# stereo_mix_back_digital.net
KiCad netlist of a schematic drawn in EAGLE
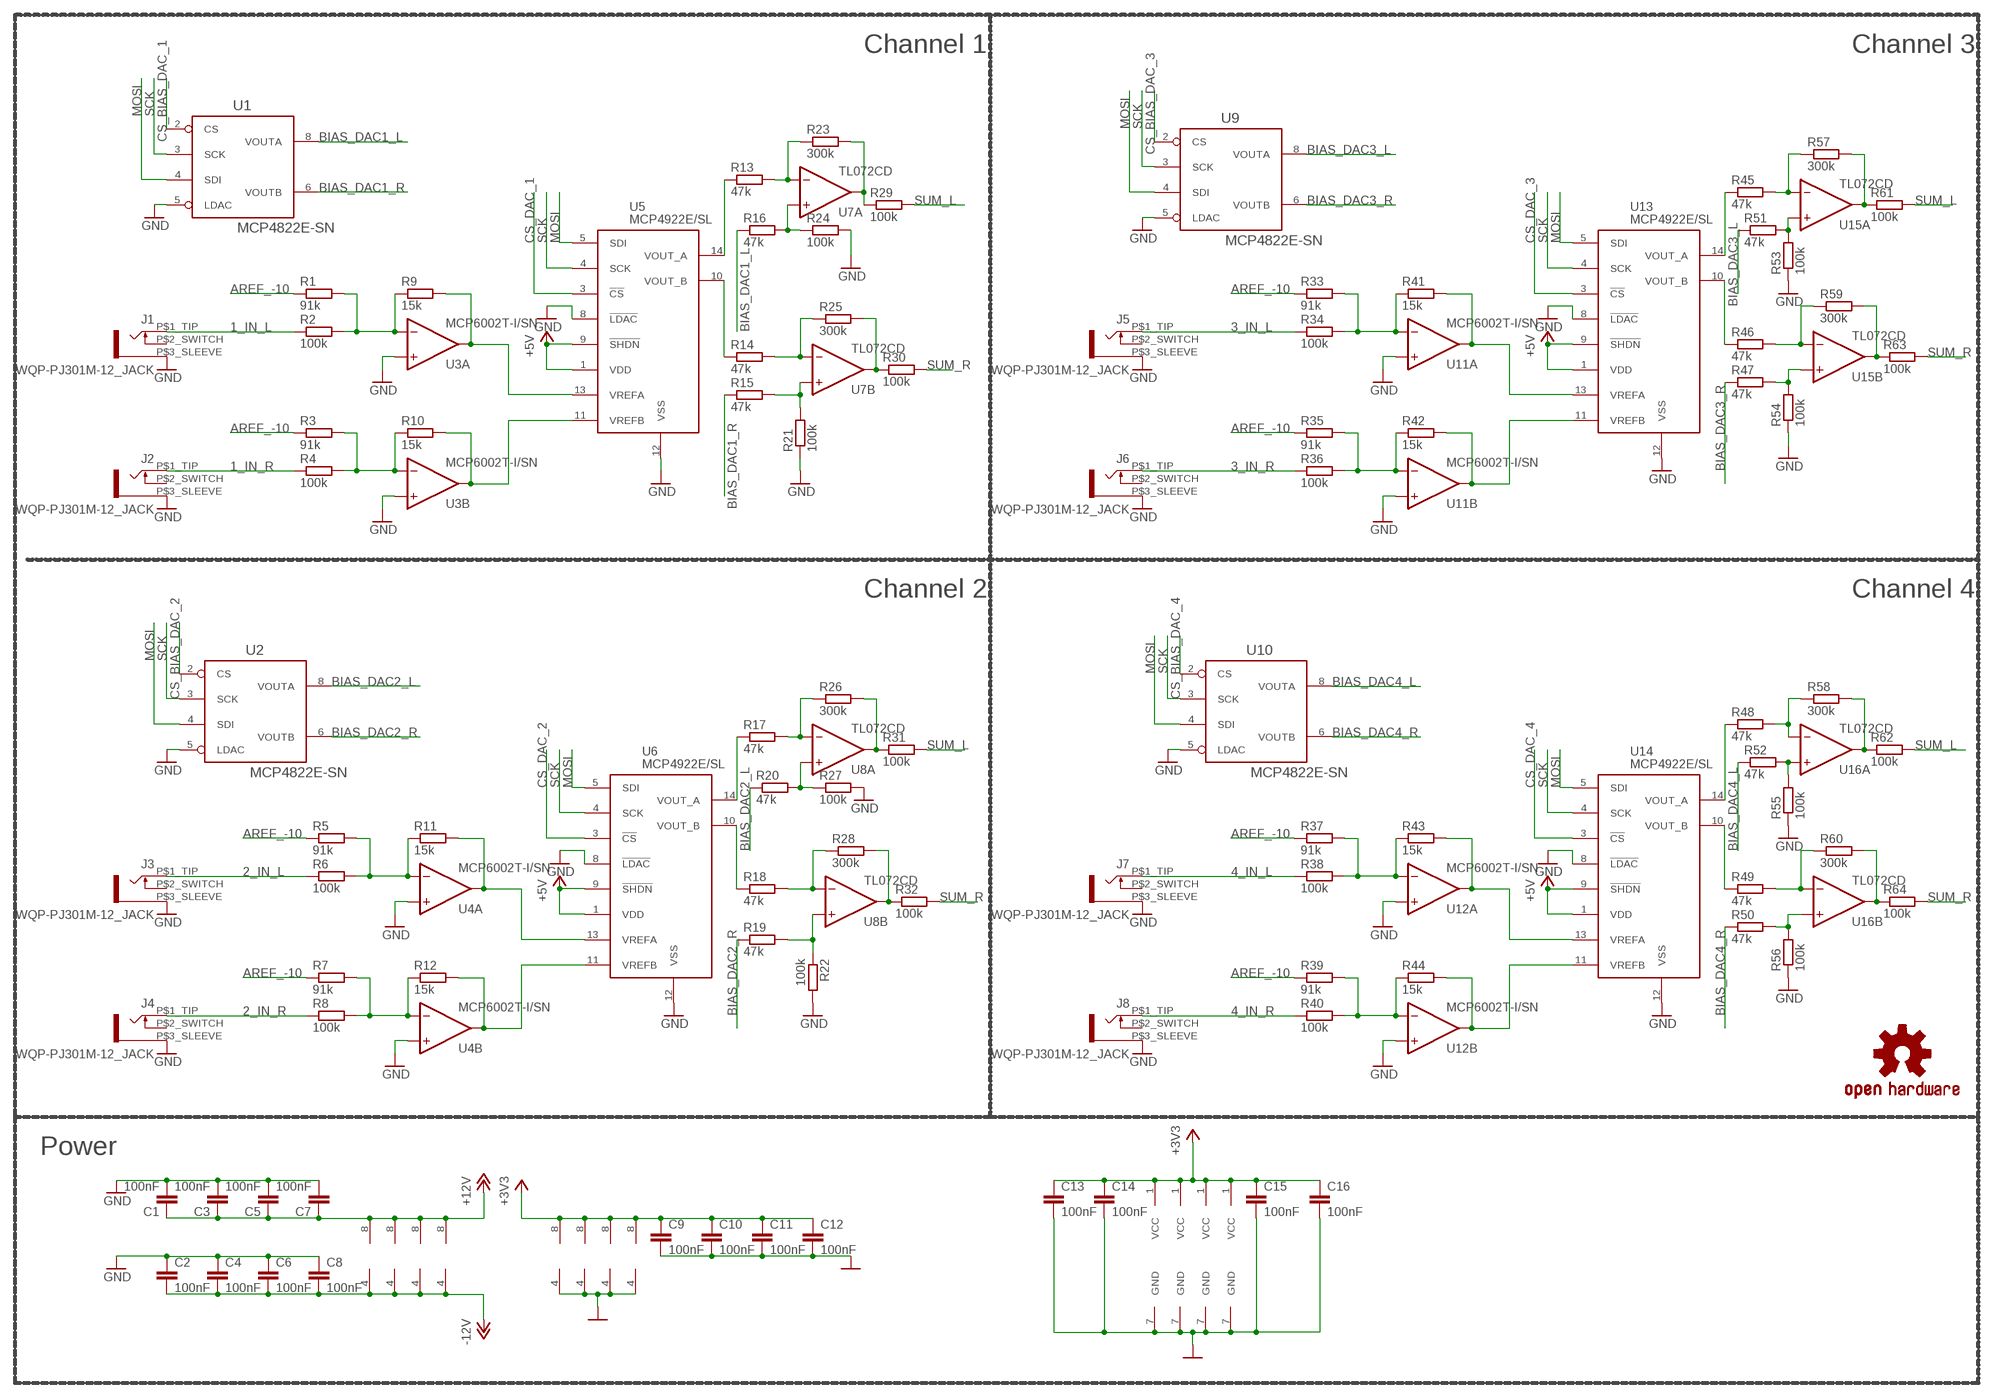
[diagram p0: schematic, sheet 1]
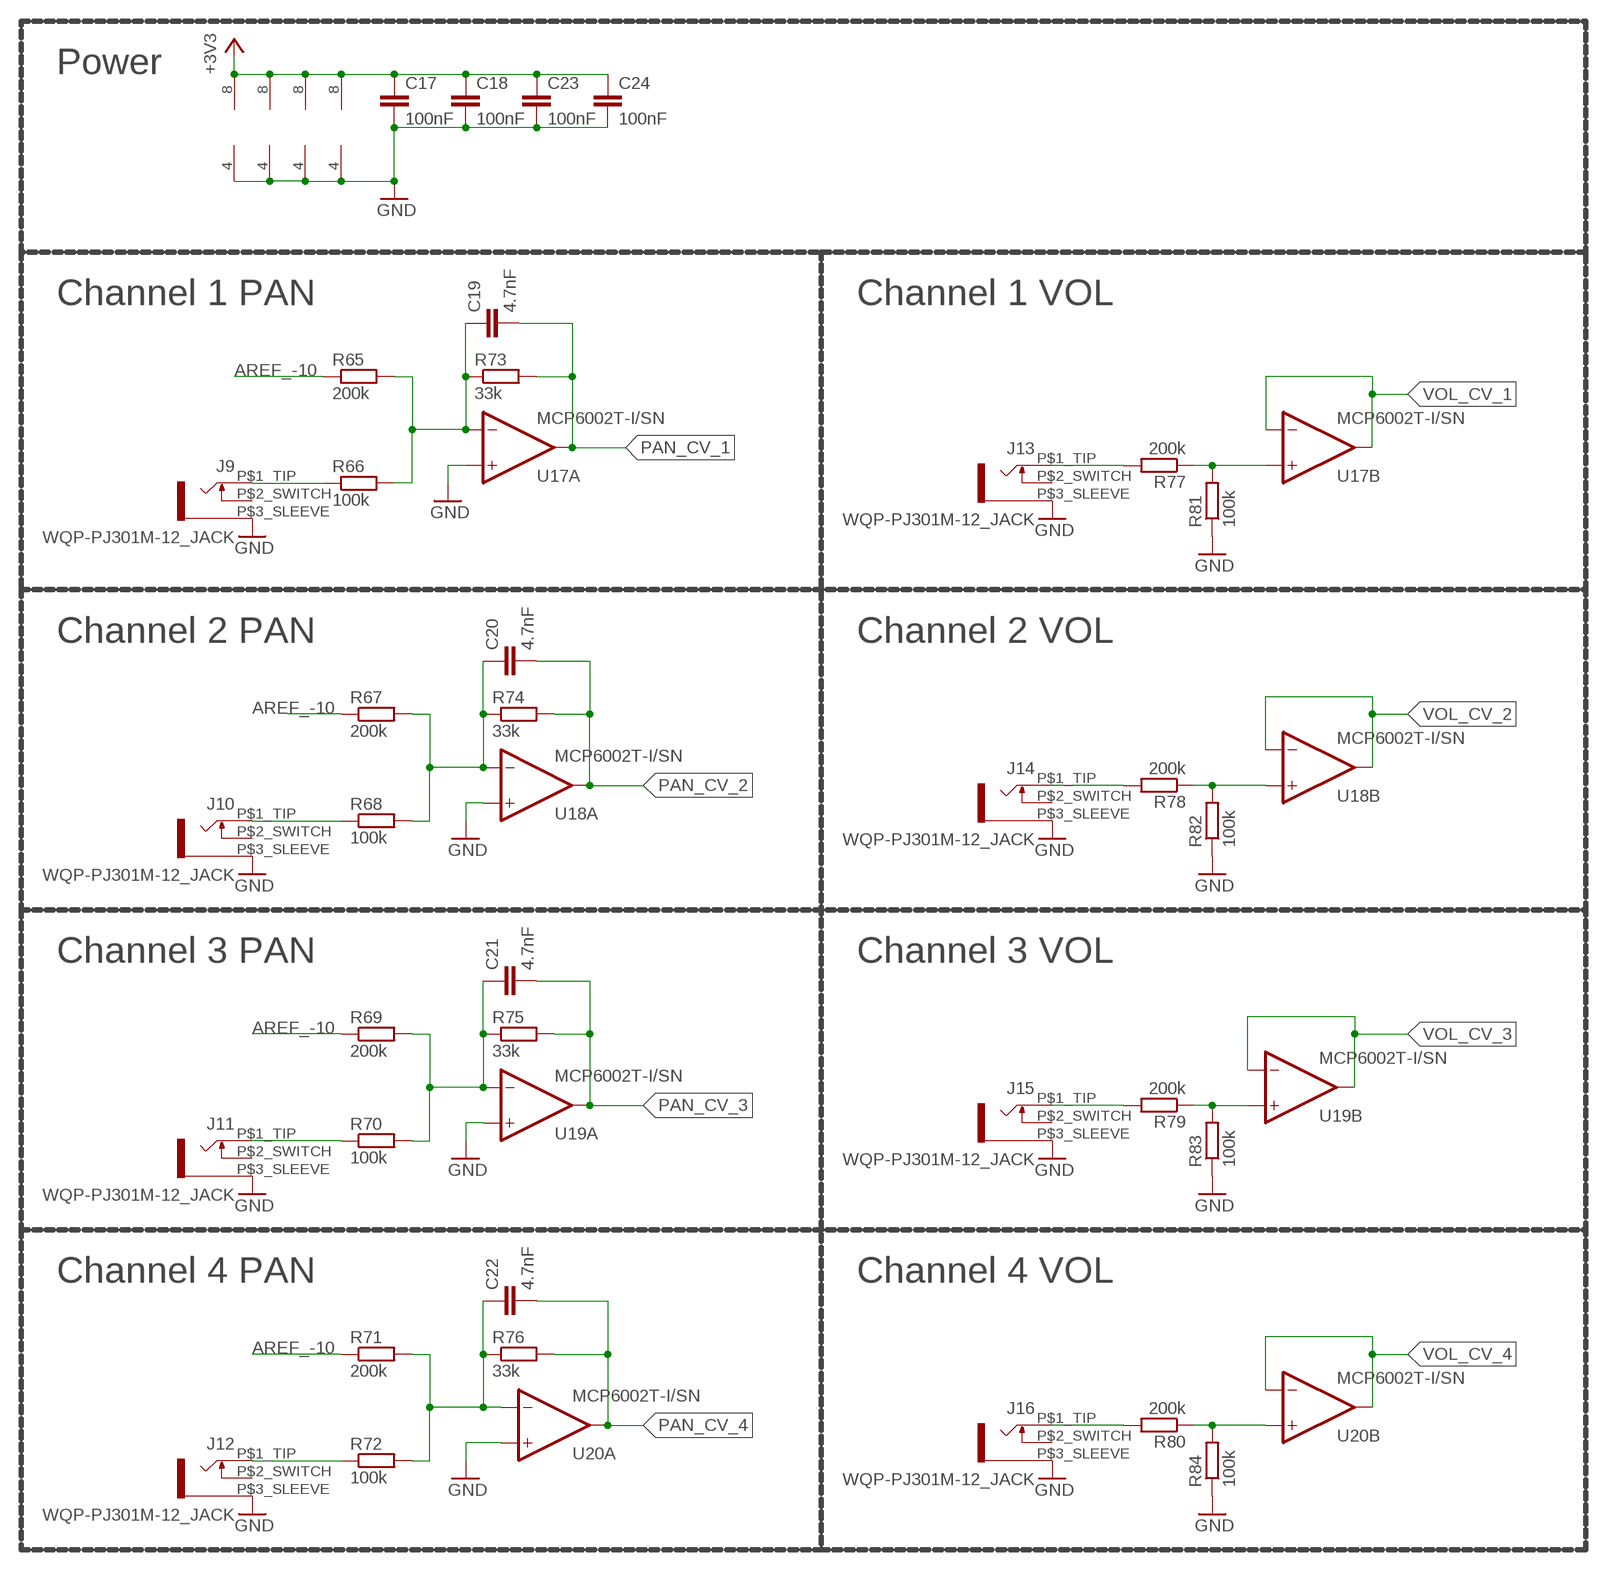
[diagram p1: schematic, sheet 2]
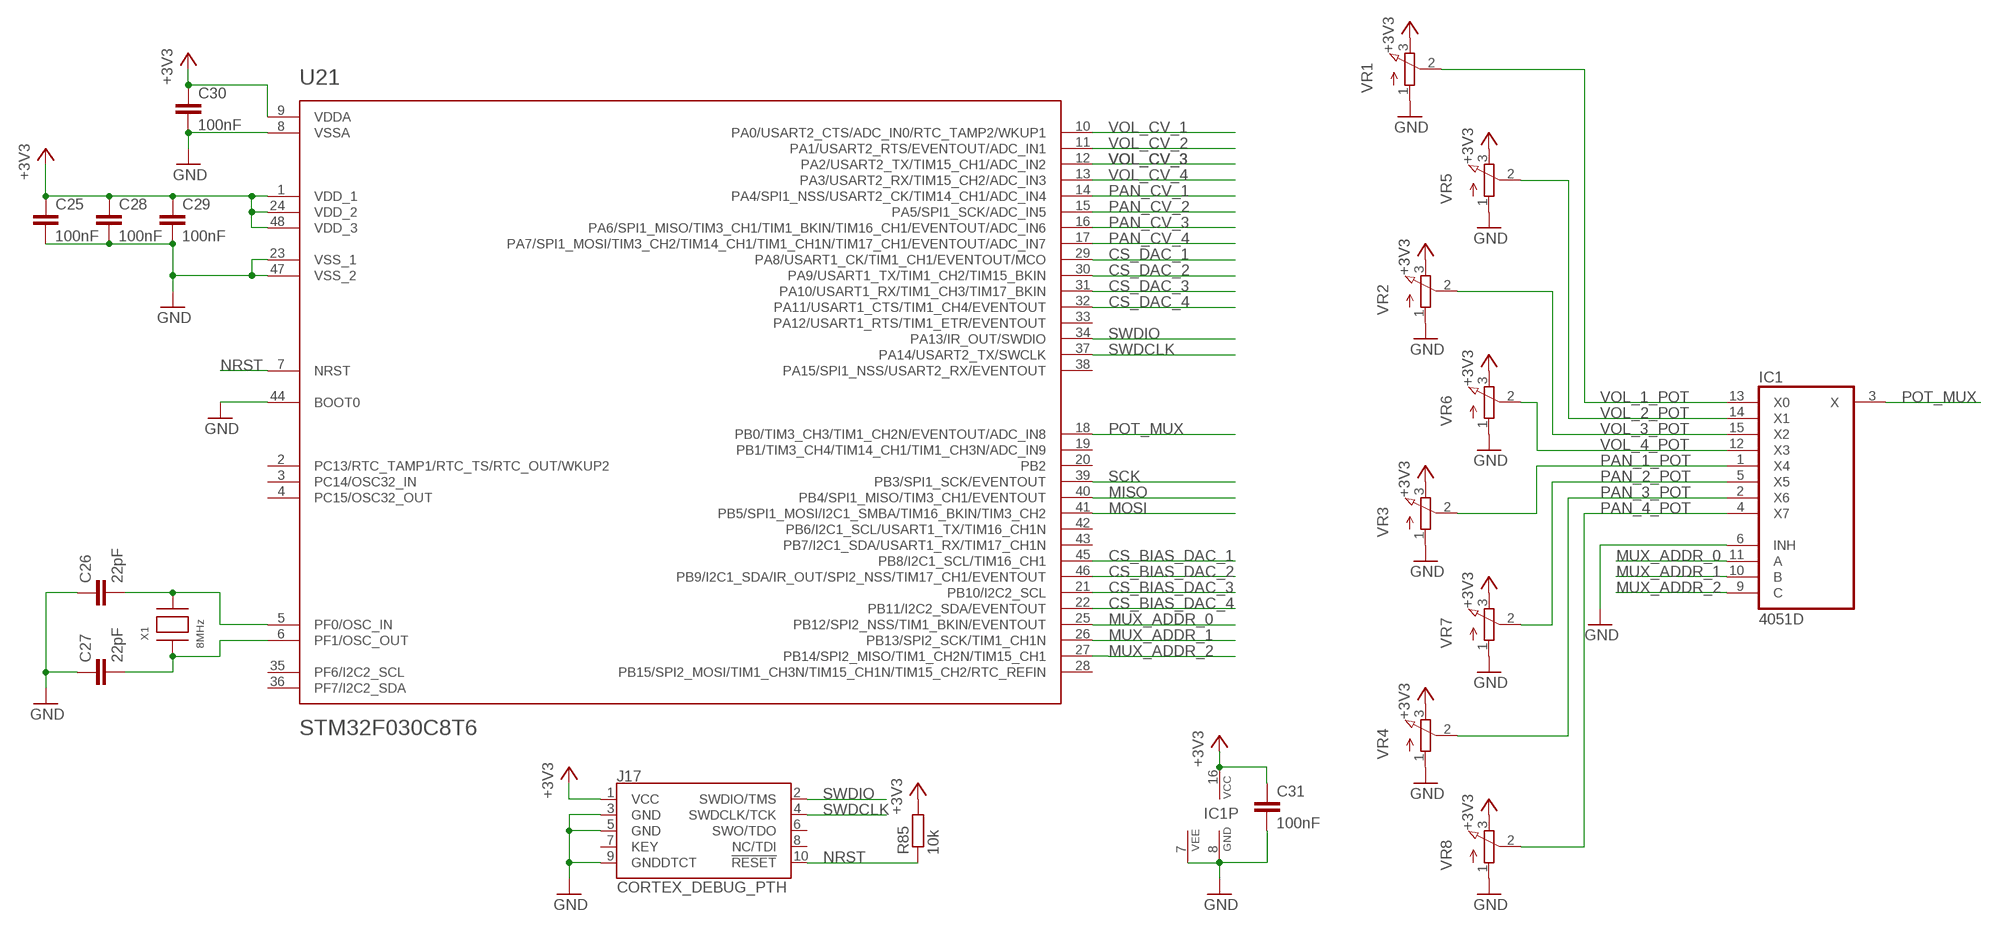
[diagram p2: schematic, sheet 3]
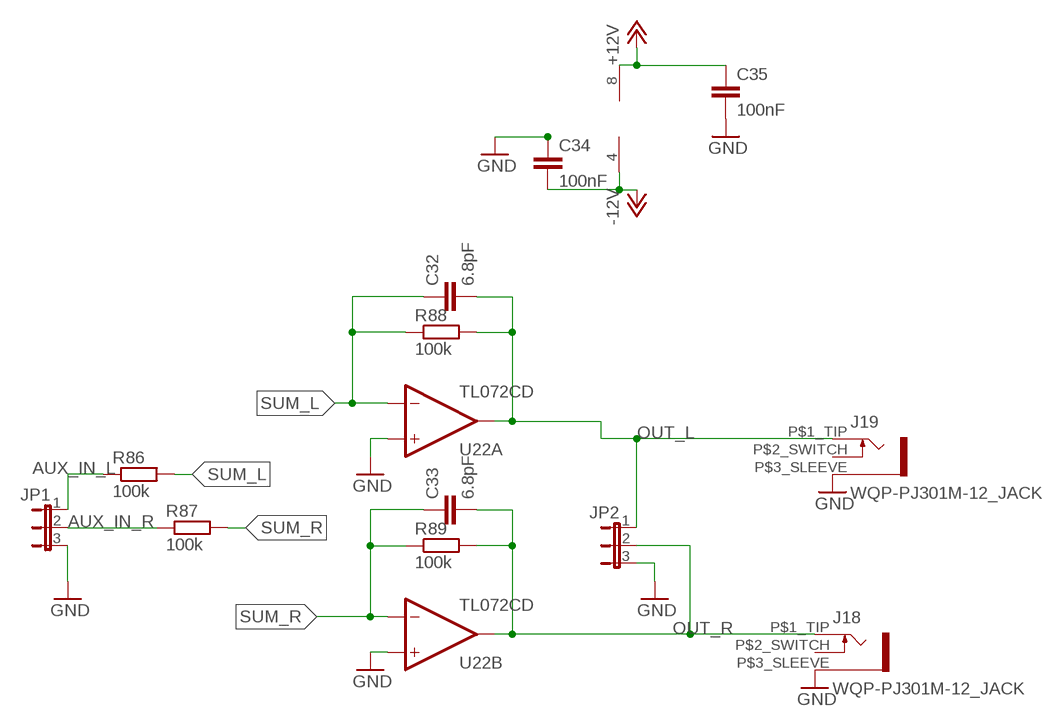
[diagram p3: schematic, sheet 4]
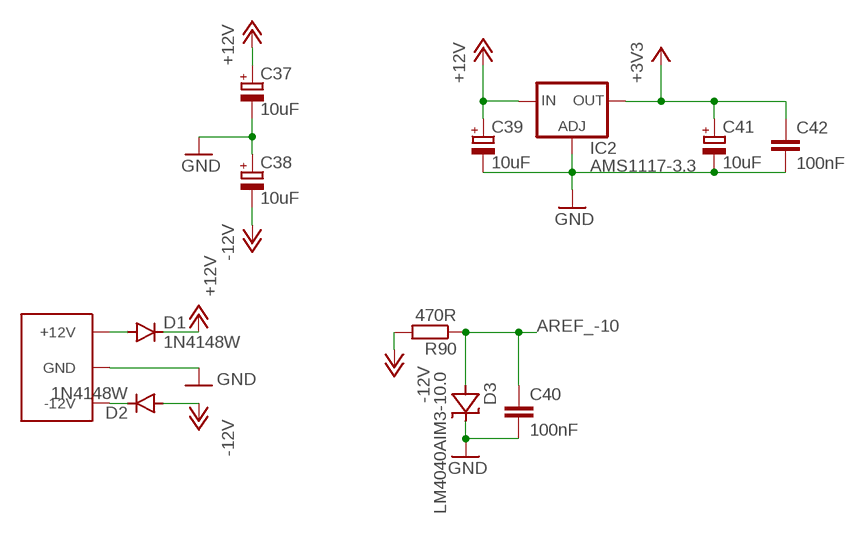
[diagram p4: schematic, sheet 5]

(export (version "E")
  (design (tool "Eeschema 10.0.6"))
  (components
    (comp (ref "C25")
      (value "100nF")
      (footprint "eagle-import:C0402")
      (libsource (lib "eagle-import") (part "C-EUC0402"))
    )
    (comp (ref "C26")
      (value "22pF")
      (footprint "eagle-import:C0402")
      (libsource (lib "eagle-import") (part "C-EUC0402"))
    )
    (comp (ref "C27")
      (value "22pF")
      (footprint "eagle-import:C0402")
      (libsource (lib "eagle-import") (part "C-EUC0402"))
    )
    (comp (ref "C28")
      (value "100nF")
      (footprint "eagle-import:C0402")
      (libsource (lib "eagle-import") (part "C-EUC0402"))
    )
    (comp (ref "C29")
      (value "100nF")
      (footprint "eagle-import:C0402")
      (libsource (lib "eagle-import") (part "C-EUC0402"))
    )
    (comp (ref "C30")
      (value "100nF")
      (footprint "eagle-import:C0402")
      (libsource (lib "eagle-import") (part "C-EUC0402"))
    )
    (comp (ref "C31")
      (value "100nF")
      (footprint "eagle-import:C0402")
      (libsource (lib "eagle-import") (part "C-EUC0402"))
    )
    (comp (ref "IC1")
      (value "4051D")
      (footprint "eagle-import:SO16")
      (libsource (lib "eagle-import") (part "4051D"))
    )
    (comp (ref "J17")
      (value "CORTEX_DEBUG_PTH")
      (footprint "eagle-import:2X5-PTH-1.27MM")
      (libsource (lib "eagle-import") (part "CORTEX_DEBUG_PTH"))
    )
    (comp (ref "R85")
      (value "10k")
      (footprint "eagle-import:R0402")
      (libsource (lib "eagle-import") (part "R-EU_R0402"))
    )
    (comp (ref "U21")
      (value "STM32F030C8T6")
      (footprint "eagle-import:LQFP48")
      (libsource (lib "eagle-import") (part "STM32F030C8T6"))
    )
    (comp (ref "VR1")
      (value "9MM_SNAP-IN_POT_")
      (footprint "eagle-import:9MM_SNAP-IN_POT")
      (libsource (lib "eagle-import") (part "9MM_SNAP-IN_POT_"))
    )
    (comp (ref "VR2")
      (value "9MM_SNAP-IN_POT_")
      (footprint "eagle-import:9MM_SNAP-IN_POT")
      (libsource (lib "eagle-import") (part "9MM_SNAP-IN_POT_"))
    )
    (comp (ref "VR3")
      (value "9MM_SNAP-IN_POT_")
      (footprint "eagle-import:9MM_SNAP-IN_POT")
      (libsource (lib "eagle-import") (part "9MM_SNAP-IN_POT_"))
    )
    (comp (ref "VR4")
      (value "9MM_SNAP-IN_POT_")
      (footprint "eagle-import:9MM_SNAP-IN_POT")
      (libsource (lib "eagle-import") (part "9MM_SNAP-IN_POT_"))
    )
    (comp (ref "VR5")
      (value "9MM_SNAP-IN_POT_")
      (footprint "eagle-import:9MM_SNAP-IN_POT")
      (libsource (lib "eagle-import") (part "9MM_SNAP-IN_POT_"))
    )
    (comp (ref "VR6")
      (value "9MM_SNAP-IN_POT_")
      (footprint "eagle-import:9MM_SNAP-IN_POT")
      (libsource (lib "eagle-import") (part "9MM_SNAP-IN_POT_"))
    )
    (comp (ref "VR7")
      (value "9MM_SNAP-IN_POT_")
      (footprint "eagle-import:9MM_SNAP-IN_POT")
      (libsource (lib "eagle-import") (part "9MM_SNAP-IN_POT_"))
    )
    (comp (ref "VR8")
      (value "9MM_SNAP-IN_POT_")
      (footprint "eagle-import:9MM_SNAP-IN_POT")
      (libsource (lib "eagle-import") (part "9MM_SNAP-IN_POT_"))
    )
    (comp (ref "X1")
      (value "8MHz")
      (footprint "eagle-import:NX5032")
      (libsource (lib "eagle-import") (part "XTALNX5032"))
    )
    (comp (ref "C1")
      (value "100nF")
      (footprint "eagle-import:C0402")
      (libsource (lib "eagle-import") (part "C-EUC0402"))
    )
    (comp (ref "C2")
      (value "100nF")
      (footprint "eagle-import:C0402")
      (libsource (lib "eagle-import") (part "C-EUC0402"))
    )
    (comp (ref "C3")
      (value "100nF")
      (footprint "eagle-import:C0402")
      (libsource (lib "eagle-import") (part "C-EUC0402"))
    )
    (comp (ref "C4")
      (value "100nF")
      (footprint "eagle-import:C0402")
      (libsource (lib "eagle-import") (part "C-EUC0402"))
    )
    (comp (ref "C5")
      (value "100nF")
      (footprint "eagle-import:C0402")
      (libsource (lib "eagle-import") (part "C-EUC0402"))
    )
    (comp (ref "C6")
      (value "100nF")
      (footprint "eagle-import:C0402")
      (libsource (lib "eagle-import") (part "C-EUC0402"))
    )
    (comp (ref "C7")
      (value "100nF")
      (footprint "eagle-import:C0402")
      (libsource (lib "eagle-import") (part "C-EUC0402"))
    )
    (comp (ref "C8")
      (value "100nF")
      (footprint "eagle-import:C0402")
      (libsource (lib "eagle-import") (part "C-EUC0402"))
    )
    (comp (ref "C9")
      (value "100nF")
      (footprint "eagle-import:C0402")
      (libsource (lib "eagle-import") (part "C-EUC0402"))
    )
    (comp (ref "C10")
      (value "100nF")
      (footprint "eagle-import:C0402")
      (libsource (lib "eagle-import") (part "C-EUC0402"))
    )
    (comp (ref "C11")
      (value "100nF")
      (footprint "eagle-import:C0402")
      (libsource (lib "eagle-import") (part "C-EUC0402"))
    )
    (comp (ref "C12")
      (value "100nF")
      (footprint "eagle-import:C0402")
      (libsource (lib "eagle-import") (part "C-EUC0402"))
    )
    (comp (ref "C13")
      (value "100nF")
      (footprint "eagle-import:C0402")
      (libsource (lib "eagle-import") (part "C-EUC0402"))
    )
    (comp (ref "C14")
      (value "100nF")
      (footprint "eagle-import:C0402")
      (libsource (lib "eagle-import") (part "C-EUC0402"))
    )
    (comp (ref "C15")
      (value "100nF")
      (footprint "eagle-import:C0402")
      (libsource (lib "eagle-import") (part "C-EUC0402"))
    )
    (comp (ref "C16")
      (value "100nF")
      (footprint "eagle-import:C0402")
      (libsource (lib "eagle-import") (part "C-EUC0402"))
    )
    (comp (ref "J1")
      (value "WQP-PJ301M-12_JACK")
      (footprint "eagle-import:WQP-PJ301M-12_JACK")
      (libsource (lib "eagle-import") (part "WQP-PJ301M-12_JACK"))
    )
    (comp (ref "J2")
      (value "WQP-PJ301M-12_JACK")
      (footprint "eagle-import:WQP-PJ301M-12_JACK")
      (libsource (lib "eagle-import") (part "WQP-PJ301M-12_JACK"))
    )
    (comp (ref "J3")
      (value "WQP-PJ301M-12_JACK")
      (footprint "eagle-import:WQP-PJ301M-12_JACK")
      (libsource (lib "eagle-import") (part "WQP-PJ301M-12_JACK"))
    )
    (comp (ref "J4")
      (value "WQP-PJ301M-12_JACK")
      (footprint "eagle-import:WQP-PJ301M-12_JACK")
      (libsource (lib "eagle-import") (part "WQP-PJ301M-12_JACK"))
    )
    (comp (ref "J5")
      (value "WQP-PJ301M-12_JACK")
      (footprint "eagle-import:WQP-PJ301M-12_JACK")
      (libsource (lib "eagle-import") (part "WQP-PJ301M-12_JACK"))
    )
    (comp (ref "J6")
      (value "WQP-PJ301M-12_JACK")
      (footprint "eagle-import:WQP-PJ301M-12_JACK")
      (libsource (lib "eagle-import") (part "WQP-PJ301M-12_JACK"))
    )
    (comp (ref "J7")
      (value "WQP-PJ301M-12_JACK")
      (footprint "eagle-import:WQP-PJ301M-12_JACK")
      (libsource (lib "eagle-import") (part "WQP-PJ301M-12_JACK"))
    )
    (comp (ref "J8")
      (value "WQP-PJ301M-12_JACK")
      (footprint "eagle-import:WQP-PJ301M-12_JACK")
      (libsource (lib "eagle-import") (part "WQP-PJ301M-12_JACK"))
    )
    (comp (ref "LOGO1")
      (value "OSHW-LOGOS")
      (footprint "eagle-import:OSHW-LOGO-S")
      (libsource (lib "eagle-import") (part "OSHW-LOGOS"))
    )
    (comp (ref "R1")
      (value "91k")
      (footprint "eagle-import:R0402")
      (libsource (lib "eagle-import") (part "R-EU_R0402"))
    )
    (comp (ref "R2")
      (value "100k")
      (footprint "eagle-import:R0402")
      (libsource (lib "eagle-import") (part "R-EU_R0402"))
    )
    (comp (ref "R3")
      (value "91k")
      (footprint "eagle-import:R0402")
      (libsource (lib "eagle-import") (part "R-EU_R0402"))
    )
    (comp (ref "R4")
      (value "100k")
      (footprint "eagle-import:R0402")
      (libsource (lib "eagle-import") (part "R-EU_R0402"))
    )
    (comp (ref "R5")
      (value "91k")
      (footprint "eagle-import:R0402")
      (libsource (lib "eagle-import") (part "R-EU_R0402"))
    )
    (comp (ref "R6")
      (value "100k")
      (footprint "eagle-import:R0402")
      (libsource (lib "eagle-import") (part "R-EU_R0402"))
    )
    (comp (ref "R7")
      (value "91k")
      (footprint "eagle-import:R0402")
      (libsource (lib "eagle-import") (part "R-EU_R0402"))
    )
    (comp (ref "R8")
      (value "100k")
      (footprint "eagle-import:R0402")
      (libsource (lib "eagle-import") (part "R-EU_R0402"))
    )
    (comp (ref "R9")
      (value "15k")
      (footprint "eagle-import:R0402")
      (libsource (lib "eagle-import") (part "R-EU_R0402"))
    )
    (comp (ref "R10")
      (value "15k")
      (footprint "eagle-import:R0402")
      (libsource (lib "eagle-import") (part "R-EU_R0402"))
    )
    (comp (ref "R11")
      (value "15k")
      (footprint "eagle-import:R0402")
      (libsource (lib "eagle-import") (part "R-EU_R0402"))
    )
    (comp (ref "R12")
      (value "15k")
      (footprint "eagle-import:R0402")
      (libsource (lib "eagle-import") (part "R-EU_R0402"))
    )
    (comp (ref "R13")
      (value "47k")
      (footprint "eagle-import:R0402")
      (libsource (lib "eagle-import") (part "R-EU_R0402"))
    )
    (comp (ref "R14")
      (value "47k")
      (footprint "eagle-import:R0402")
      (libsource (lib "eagle-import") (part "R-EU_R0402"))
    )
    (comp (ref "R15")
      (value "47k")
      (footprint "eagle-import:R0402")
      (libsource (lib "eagle-import") (part "R-EU_R0402"))
    )
    (comp (ref "R16")
      (value "47k")
      (footprint "eagle-import:R0402")
      (libsource (lib "eagle-import") (part "R-EU_R0402"))
    )
    (comp (ref "R17")
      (value "47k")
      (footprint "eagle-import:R0402")
      (libsource (lib "eagle-import") (part "R-EU_R0402"))
    )
    (comp (ref "R18")
      (value "47k")
      (footprint "eagle-import:R0402")
      (libsource (lib "eagle-import") (part "R-EU_R0402"))
    )
    (comp (ref "R19")
      (value "47k")
      (footprint "eagle-import:R0402")
      (libsource (lib "eagle-import") (part "R-EU_R0402"))
    )
    (comp (ref "R20")
      (value "47k")
      (footprint "eagle-import:R0402")
      (libsource (lib "eagle-import") (part "R-EU_R0402"))
    )
    (comp (ref "R21")
      (value "100k")
      (footprint "eagle-import:R0402")
      (libsource (lib "eagle-import") (part "R-EU_R0402"))
    )
    (comp (ref "R22")
      (value "100k")
      (footprint "eagle-import:R0402")
      (libsource (lib "eagle-import") (part "R-EU_R0402"))
    )
    (comp (ref "R23")
      (value "300k")
      (footprint "eagle-import:R0402")
      (libsource (lib "eagle-import") (part "R-EU_R0402"))
    )
    (comp (ref "R24")
      (value "100k")
      (footprint "eagle-import:R0402")
      (libsource (lib "eagle-import") (part "R-EU_R0402"))
    )
    (comp (ref "R25")
      (value "300k")
      (footprint "eagle-import:R0402")
      (libsource (lib "eagle-import") (part "R-EU_R0402"))
    )
    (comp (ref "R26")
      (value "300k")
      (footprint "eagle-import:R0402")
      (libsource (lib "eagle-import") (part "R-EU_R0402"))
    )
    (comp (ref "R27")
      (value "100k")
      (footprint "eagle-import:R0402")
      (libsource (lib "eagle-import") (part "R-EU_R0402"))
    )
    (comp (ref "R28")
      (value "300k")
      (footprint "eagle-import:R0402")
      (libsource (lib "eagle-import") (part "R-EU_R0402"))
    )
    (comp (ref "R29")
      (value "100k")
      (footprint "eagle-import:R0402")
      (libsource (lib "eagle-import") (part "R-EU_R0402"))
    )
    (comp (ref "R30")
      (value "100k")
      (footprint "eagle-import:R0402")
      (libsource (lib "eagle-import") (part "R-EU_R0402"))
    )
    (comp (ref "R31")
      (value "100k")
      (footprint "eagle-import:R0402")
      (libsource (lib "eagle-import") (part "R-EU_R0402"))
    )
    (comp (ref "R32")
      (value "100k")
      (footprint "eagle-import:R0402")
      (libsource (lib "eagle-import") (part "R-EU_R0402"))
    )
    (comp (ref "R33")
      (value "91k")
      (footprint "eagle-import:R0402")
      (libsource (lib "eagle-import") (part "R-EU_R0402"))
    )
    (comp (ref "R34")
      (value "100k")
      (footprint "eagle-import:R0402")
      (libsource (lib "eagle-import") (part "R-EU_R0402"))
    )
    (comp (ref "R35")
      (value "91k")
      (footprint "eagle-import:R0402")
      (libsource (lib "eagle-import") (part "R-EU_R0402"))
    )
    (comp (ref "R36")
      (value "100k")
      (footprint "eagle-import:R0402")
      (libsource (lib "eagle-import") (part "R-EU_R0402"))
    )
    (comp (ref "R37")
      (value "91k")
      (footprint "eagle-import:R0402")
      (libsource (lib "eagle-import") (part "R-EU_R0402"))
    )
    (comp (ref "R38")
      (value "100k")
      (footprint "eagle-import:R0402")
      (libsource (lib "eagle-import") (part "R-EU_R0402"))
    )
    (comp (ref "R39")
      (value "91k")
      (footprint "eagle-import:R0402")
      (libsource (lib "eagle-import") (part "R-EU_R0402"))
    )
    (comp (ref "R40")
      (value "100k")
      (footprint "eagle-import:R0402")
      (libsource (lib "eagle-import") (part "R-EU_R0402"))
    )
    (comp (ref "R41")
      (value "15k")
      (footprint "eagle-import:R0402")
      (libsource (lib "eagle-import") (part "R-EU_R0402"))
    )
    (comp (ref "R42")
      (value "15k")
      (footprint "eagle-import:R0402")
      (libsource (lib "eagle-import") (part "R-EU_R0402"))
    )
    (comp (ref "R43")
      (value "15k")
      (footprint "eagle-import:R0402")
      (libsource (lib "eagle-import") (part "R-EU_R0402"))
    )
    (comp (ref "R44")
      (value "15k")
      (footprint "eagle-import:R0402")
      (libsource (lib "eagle-import") (part "R-EU_R0402"))
    )
    (comp (ref "R45")
      (value "47k")
      (footprint "eagle-import:R0402")
      (libsource (lib "eagle-import") (part "R-EU_R0402"))
    )
    (comp (ref "R46")
      (value "47k")
      (footprint "eagle-import:R0402")
      (libsource (lib "eagle-import") (part "R-EU_R0402"))
    )
    (comp (ref "R47")
      (value "47k")
      (footprint "eagle-import:R0402")
      (libsource (lib "eagle-import") (part "R-EU_R0402"))
    )
    (comp (ref "R48")
      (value "47k")
      (footprint "eagle-import:R0402")
      (libsource (lib "eagle-import") (part "R-EU_R0402"))
    )
    (comp (ref "R49")
      (value "47k")
      (footprint "eagle-import:R0402")
      (libsource (lib "eagle-import") (part "R-EU_R0402"))
    )
    (comp (ref "R50")
      (value "47k")
      (footprint "eagle-import:R0402")
      (libsource (lib "eagle-import") (part "R-EU_R0402"))
    )
    (comp (ref "R51")
      (value "47k")
      (footprint "eagle-import:R0402")
      (libsource (lib "eagle-import") (part "R-EU_R0402"))
    )
    (comp (ref "R52")
      (value "47k")
      (footprint "eagle-import:R0402")
      (libsource (lib "eagle-import") (part "R-EU_R0402"))
    )
    (comp (ref "R53")
      (value "100k")
      (footprint "eagle-import:R0402")
      (libsource (lib "eagle-import") (part "R-EU_R0402"))
    )
    (comp (ref "R54")
      (value "100k")
      (footprint "eagle-import:R0402")
      (libsource (lib "eagle-import") (part "R-EU_R0402"))
    )
    (comp (ref "R55")
      (value "100k")
      (footprint "eagle-import:R0402")
      (libsource (lib "eagle-import") (part "R-EU_R0402"))
    )
    (comp (ref "R56")
      (value "100k")
      (footprint "eagle-import:R0402")
      (libsource (lib "eagle-import") (part "R-EU_R0402"))
    )
    (comp (ref "R57")
      (value "300k")
      (footprint "eagle-import:R0402")
      (libsource (lib "eagle-import") (part "R-EU_R0402"))
    )
    (comp (ref "R58")
      (value "300k")
      (footprint "eagle-import:R0402")
      (libsource (lib "eagle-import") (part "R-EU_R0402"))
    )
    (comp (ref "R59")
      (value "300k")
      (footprint "eagle-import:R0402")
      (libsource (lib "eagle-import") (part "R-EU_R0402"))
    )
    (comp (ref "R60")
      (value "300k")
      (footprint "eagle-import:R0402")
      (libsource (lib "eagle-import") (part "R-EU_R0402"))
    )
    (comp (ref "R61")
      (value "100k")
      (footprint "eagle-import:R0402")
      (libsource (lib "eagle-import") (part "R-EU_R0402"))
    )
    (comp (ref "R62")
      (value "100k")
      (footprint "eagle-import:R0402")
      (libsource (lib "eagle-import") (part "R-EU_R0402"))
    )
    (comp (ref "R63")
      (value "100k")
      (footprint "eagle-import:R0402")
      (libsource (lib "eagle-import") (part "R-EU_R0402"))
    )
    (comp (ref "R64")
      (value "100k")
      (footprint "eagle-import:R0402")
      (libsource (lib "eagle-import") (part "R-EU_R0402"))
    )
    (comp (ref "U1")
      (value "MCP4822E-SN")
      (footprint "eagle-import:SOIC8")
      (libsource (lib "eagle-import") (part "MCP482E-SN2"))
    )
    (comp (ref "U2")
      (value "MCP4822E-SN")
      (footprint "eagle-import:SOIC8")
      (libsource (lib "eagle-import") (part "MCP482E-SN2"))
    )
    (comp (ref "U3")
      (value "MCP6002T-I/SN")
      (footprint "eagle-import:SOIC8")
      (libsource (lib "eagle-import") (part "MCP6002T-I/SN"))
    )
    (comp (ref "U4")
      (value "MCP6002T-I/SN")
      (footprint "eagle-import:SOIC8")
      (libsource (lib "eagle-import") (part "MCP6002T-I/SN"))
    )
    (comp (ref "U5")
      (value "MCP4922E/SL")
      (footprint "eagle-import:SO-14")
      (libsource (lib "eagle-import") (part "MCP492E/SL2"))
    )
    (comp (ref "U6")
      (value "MCP4922E/SL")
      (footprint "eagle-import:SO-14")
      (libsource (lib "eagle-import") (part "MCP492E/SL2"))
    )
    (comp (ref "U7")
      (value "TL072CD")
      (footprint "eagle-import:SOIC8")
      (libsource (lib "eagle-import") (part "TL072DC"))
    )
    (comp (ref "U8")
      (value "TL072CD")
      (footprint "eagle-import:SOIC8")
      (libsource (lib "eagle-import") (part "TL072DC"))
    )
    (comp (ref "U9")
      (value "MCP4822E-SN")
      (footprint "eagle-import:SOIC8")
      (libsource (lib "eagle-import") (part "MCP482E-SN2"))
    )
    (comp (ref "U10")
      (value "MCP4822E-SN")
      (footprint "eagle-import:SOIC8")
      (libsource (lib "eagle-import") (part "MCP482E-SN2"))
    )
    (comp (ref "U11")
      (value "MCP6002T-I/SN")
      (footprint "eagle-import:SOIC8")
      (libsource (lib "eagle-import") (part "MCP6002T-I/SN"))
    )
    (comp (ref "U12")
      (value "MCP6002T-I/SN")
      (footprint "eagle-import:SOIC8")
      (libsource (lib "eagle-import") (part "MCP6002T-I/SN"))
    )
    (comp (ref "U13")
      (value "MCP4922E/SL")
      (footprint "eagle-import:SO-14")
      (libsource (lib "eagle-import") (part "MCP492E/SL2"))
    )
    (comp (ref "U14")
      (value "MCP4922E/SL")
      (footprint "eagle-import:SO-14")
      (libsource (lib "eagle-import") (part "MCP492E/SL2"))
    )
    (comp (ref "U15")
      (value "TL072CD")
      (footprint "eagle-import:SOIC8")
      (libsource (lib "eagle-import") (part "TL072DC"))
    )
    (comp (ref "U16")
      (value "TL072CD")
      (footprint "eagle-import:SOIC8")
      (libsource (lib "eagle-import") (part "TL072DC"))
    )
    (comp (ref "C36")
      (value "EURO_POWER_LOCKFAT-LOCK")
      (footprint "eagle-import:EURO_PWR_HEADER_LOCK")
      (libsource (lib "eagle-import") (part "EURO_POWER_LOCKFAT-LOCK"))
    )
    (comp (ref "C37")
      (value "10uF")
      (footprint "eagle-import:A_3216-18R")
      (libsource (lib "eagle-import") (part "CPOL-EUA/3216-18R"))
    )
    (comp (ref "C38")
      (value "10uF")
      (footprint "eagle-import:A_3216-18R")
      (libsource (lib "eagle-import") (part "CPOL-EUA/3216-18R"))
    )
    (comp (ref "C39")
      (value "10uF")
      (footprint "eagle-import:A_3216-18R")
      (libsource (lib "eagle-import") (part "CPOL-EUA/3216-18R"))
    )
    (comp (ref "C40")
      (value "100nF")
      (footprint "eagle-import:C0402")
      (libsource (lib "eagle-import") (part "C-EUC0402"))
    )
    (comp (ref "C41")
      (value "10uF")
      (footprint "eagle-import:A_3216-18R")
      (libsource (lib "eagle-import") (part "CPOL-EUA/3216-18R"))
    )
    (comp (ref "C42")
      (value "100nF")
      (footprint "eagle-import:C0402")
      (libsource (lib "eagle-import") (part "C-EUC0402"))
    )
    (comp (ref "D1")
      (value "1N4148W")
      (footprint "eagle-import:SOD123")
      (libsource (lib "eagle-import") (part "DIODE-SOD123"))
    )
    (comp (ref "D2")
      (value "1N4148W")
      (footprint "eagle-import:SOD123")
      (libsource (lib "eagle-import") (part "DIODE-SOD123"))
    )
    (comp (ref "D3")
      (value "LM4040AIM3-10.0")
      (footprint "eagle-import:SOT23")
      (libsource (lib "eagle-import") (part "LM4040-10.0AIM3"))
    )
    (comp (ref "IC2")
      (value "AMS1117-3.3")
      (footprint "eagle-import:SOT223")
      (libsource (lib "eagle-import") (part "AMS1117-3.3"))
    )
    (comp (ref "R90")
      (value "470R")
      (footprint "eagle-import:R0402")
      (libsource (lib "eagle-import") (part "R-EU_R0402"))
    )
    (comp (ref "C17")
      (value "100nF")
      (footprint "eagle-import:C0402")
      (libsource (lib "eagle-import") (part "C-EUC0402"))
    )
    (comp (ref "C18")
      (value "100nF")
      (footprint "eagle-import:C0402")
      (libsource (lib "eagle-import") (part "C-EUC0402"))
    )
    (comp (ref "C19")
      (value "4.7nF")
      (footprint "eagle-import:C0402")
      (libsource (lib "eagle-import") (part "C-EUC0402"))
    )
    (comp (ref "C20")
      (value "4.7nF")
      (footprint "eagle-import:C0402")
      (libsource (lib "eagle-import") (part "C-EUC0402"))
    )
    (comp (ref "C21")
      (value "4.7nF")
      (footprint "eagle-import:C0402")
      (libsource (lib "eagle-import") (part "C-EUC0402"))
    )
    (comp (ref "C22")
      (value "4.7nF")
      (footprint "eagle-import:C0402")
      (libsource (lib "eagle-import") (part "C-EUC0402"))
    )
    (comp (ref "C23")
      (value "100nF")
      (footprint "eagle-import:C0402")
      (libsource (lib "eagle-import") (part "C-EUC0402"))
    )
    (comp (ref "C24")
      (value "100nF")
      (footprint "eagle-import:C0402")
      (libsource (lib "eagle-import") (part "C-EUC0402"))
    )
    (comp (ref "J9")
      (value "WQP-PJ301M-12_JACK")
      (footprint "eagle-import:WQP-PJ301M-12_JACK")
      (libsource (lib "eagle-import") (part "WQP-PJ301M-12_JACK"))
    )
    (comp (ref "J10")
      (value "WQP-PJ301M-12_JACK")
      (footprint "eagle-import:WQP-PJ301M-12_JACK")
      (libsource (lib "eagle-import") (part "WQP-PJ301M-12_JACK"))
    )
    (comp (ref "J11")
      (value "WQP-PJ301M-12_JACK")
      (footprint "eagle-import:WQP-PJ301M-12_JACK")
      (libsource (lib "eagle-import") (part "WQP-PJ301M-12_JACK"))
    )
    (comp (ref "J12")
      (value "WQP-PJ301M-12_JACK")
      (footprint "eagle-import:WQP-PJ301M-12_JACK")
      (libsource (lib "eagle-import") (part "WQP-PJ301M-12_JACK"))
    )
    (comp (ref "J13")
      (value "WQP-PJ301M-12_JACK")
      (footprint "eagle-import:WQP-PJ301M-12_JACK")
      (libsource (lib "eagle-import") (part "WQP-PJ301M-12_JACK"))
    )
    (comp (ref "J14")
      (value "WQP-PJ301M-12_JACK")
      (footprint "eagle-import:WQP-PJ301M-12_JACK")
      (libsource (lib "eagle-import") (part "WQP-PJ301M-12_JACK"))
    )
    (comp (ref "J15")
      (value "WQP-PJ301M-12_JACK")
      (footprint "eagle-import:WQP-PJ301M-12_JACK")
      (libsource (lib "eagle-import") (part "WQP-PJ301M-12_JACK"))
    )
    (comp (ref "J16")
      (value "WQP-PJ301M-12_JACK")
      (footprint "eagle-import:WQP-PJ301M-12_JACK")
      (libsource (lib "eagle-import") (part "WQP-PJ301M-12_JACK"))
    )
    (comp (ref "R65")
      (value "200k")
      (footprint "eagle-import:R0402")
      (libsource (lib "eagle-import") (part "R-EU_R0402"))
    )
    (comp (ref "R66")
      (value "100k")
      (footprint "eagle-import:R0402")
      (libsource (lib "eagle-import") (part "R-EU_R0402"))
    )
    (comp (ref "R67")
      (value "200k")
      (footprint "eagle-import:R0402")
      (libsource (lib "eagle-import") (part "R-EU_R0402"))
    )
    (comp (ref "R68")
      (value "100k")
      (footprint "eagle-import:R0402")
      (libsource (lib "eagle-import") (part "R-EU_R0402"))
    )
    (comp (ref "R69")
      (value "200k")
      (footprint "eagle-import:R0402")
      (libsource (lib "eagle-import") (part "R-EU_R0402"))
    )
    (comp (ref "R70")
      (value "100k")
      (footprint "eagle-import:R0402")
      (libsource (lib "eagle-import") (part "R-EU_R0402"))
    )
    (comp (ref "R71")
      (value "200k")
      (footprint "eagle-import:R0402")
      (libsource (lib "eagle-import") (part "R-EU_R0402"))
    )
    (comp (ref "R72")
      (value "100k")
      (footprint "eagle-import:R0402")
      (libsource (lib "eagle-import") (part "R-EU_R0402"))
    )
    (comp (ref "R73")
      (value "33k")
      (footprint "eagle-import:R0402")
      (libsource (lib "eagle-import") (part "R-EU_R0402"))
    )
    (comp (ref "R74")
      (value "33k")
      (footprint "eagle-import:R0402")
      (libsource (lib "eagle-import") (part "R-EU_R0402"))
    )
    (comp (ref "R75")
      (value "33k")
      (footprint "eagle-import:R0402")
      (libsource (lib "eagle-import") (part "R-EU_R0402"))
    )
    (comp (ref "R76")
      (value "33k")
      (footprint "eagle-import:R0402")
      (libsource (lib "eagle-import") (part "R-EU_R0402"))
    )
    (comp (ref "R77")
      (value "200k")
      (footprint "eagle-import:R0402")
      (libsource (lib "eagle-import") (part "R-EU_R0402"))
    )
    (comp (ref "R78")
      (value "200k")
      (footprint "eagle-import:R0402")
      (libsource (lib "eagle-import") (part "R-EU_R0402"))
    )
    (comp (ref "R79")
      (value "200k")
      (footprint "eagle-import:R0402")
      (libsource (lib "eagle-import") (part "R-EU_R0402"))
    )
    (comp (ref "R80")
      (value "200k")
      (footprint "eagle-import:R0402")
      (libsource (lib "eagle-import") (part "R-EU_R0402"))
    )
    (comp (ref "R81")
      (value "100k")
      (footprint "eagle-import:R0402")
      (libsource (lib "eagle-import") (part "R-EU_R0402"))
    )
    (comp (ref "R82")
      (value "100k")
      (footprint "eagle-import:R0402")
      (libsource (lib "eagle-import") (part "R-EU_R0402"))
    )
    (comp (ref "R83")
      (value "100k")
      (footprint "eagle-import:R0402")
      (libsource (lib "eagle-import") (part "R-EU_R0402"))
    )
    (comp (ref "R84")
      (value "100k")
      (footprint "eagle-import:R0402")
      (libsource (lib "eagle-import") (part "R-EU_R0402"))
    )
    (comp (ref "U17")
      (value "MCP6002T-I/SN")
      (footprint "eagle-import:SOIC8")
      (libsource (lib "eagle-import") (part "MCP6002T-I/SN"))
    )
    (comp (ref "U18")
      (value "MCP6002T-I/SN")
      (footprint "eagle-import:SOIC8")
      (libsource (lib "eagle-import") (part "MCP6002T-I/SN"))
    )
    (comp (ref "U19")
      (value "MCP6002T-I/SN")
      (footprint "eagle-import:SOIC8")
      (libsource (lib "eagle-import") (part "MCP6002T-I/SN"))
    )
    (comp (ref "U20")
      (value "MCP6002T-I/SN")
      (footprint "eagle-import:SOIC8")
      (libsource (lib "eagle-import") (part "MCP6002T-I/SN"))
    )
    (comp (ref "C32")
      (value "6.8pF")
      (footprint "eagle-import:C0402")
      (libsource (lib "eagle-import") (part "C-EUC0402"))
    )
    (comp (ref "C33")
      (value "6.8pF")
      (footprint "eagle-import:C0402")
      (libsource (lib "eagle-import") (part "C-EUC0402"))
    )
    (comp (ref "C34")
      (value "100nF")
      (footprint "eagle-import:C0402")
      (libsource (lib "eagle-import") (part "C-EUC0402"))
    )
    (comp (ref "C35")
      (value "100nF")
      (footprint "eagle-import:C0402")
      (libsource (lib "eagle-import") (part "C-EUC0402"))
    )
    (comp (ref "J18")
      (value "WQP-PJ301M-12_JACK")
      (footprint "eagle-import:WQP-PJ301M-12_JACK")
      (libsource (lib "eagle-import") (part "WQP-PJ301M-12_JACK"))
    )
    (comp (ref "J19")
      (value "WQP-PJ301M-12_JACK")
      (footprint "eagle-import:WQP-PJ301M-12_JACK")
      (libsource (lib "eagle-import") (part "WQP-PJ301M-12_JACK"))
    )
    (comp (ref "JP1")
      (value "JP2E")
      (footprint "eagle-import:JP2")
      (libsource (lib "eagle-import") (part "JP2E"))
    )
    (comp (ref "JP2")
      (value "JP2E")
      (footprint "eagle-import:JP2")
      (libsource (lib "eagle-import") (part "JP2E"))
    )
    (comp (ref "R86")
      (value "100k")
      (footprint "eagle-import:R0402")
      (libsource (lib "eagle-import") (part "R-EU_R0402"))
    )
    (comp (ref "R87")
      (value "100k")
      (footprint "eagle-import:R0402")
      (libsource (lib "eagle-import") (part "R-EU_R0402"))
    )
    (comp (ref "R88")
      (value "100k")
      (footprint "eagle-import:R0402")
      (libsource (lib "eagle-import") (part "R-EU_R0402"))
    )
    (comp (ref "R89")
      (value "100k")
      (footprint "eagle-import:R0402")
      (libsource (lib "eagle-import") (part "R-EU_R0402"))
    )
    (comp (ref "U22")
      (value "TL072CD")
      (footprint "eagle-import:SOIC8")
      (libsource (lib "eagle-import") (part "TL072DC"))
    )
  )
  (nets
    (net (code "1") (name "+3V3") (class "Default")
      (node (ref "C10") (pin "1") (pinfunction "1_1") (pintype "passive"))
      (node (ref "C11") (pin "1") (pinfunction "1_1") (pintype "passive"))
      (node (ref "C12") (pin "1") (pinfunction "1_1") (pintype "passive"))
      (node (ref "C13") (pin "1") (pinfunction "1_1") (pintype "passive"))
      (node (ref "C14") (pin "1") (pinfunction "1_1") (pintype "passive"))
      (node (ref "C15") (pin "1") (pinfunction "1_1") (pintype "passive"))
      (node (ref "C16") (pin "1") (pinfunction "1_1") (pintype "passive"))
      (node (ref "C17") (pin "1") (pinfunction "1_1") (pintype "passive"))
      (node (ref "C18") (pin "1") (pinfunction "1_1") (pintype "passive"))
      (node (ref "C23") (pin "1") (pinfunction "1_1") (pintype "passive"))
      (node (ref "C24") (pin "1") (pinfunction "1_1") (pintype "passive"))
      (node (ref "C25") (pin "1") (pinfunction "1_1") (pintype "passive"))
      (node (ref "C28") (pin "1") (pinfunction "1_1") (pintype "passive"))
      (node (ref "C29") (pin "1") (pinfunction "1_1") (pintype "passive"))
      (node (ref "C30") (pin "1") (pinfunction "1_1") (pintype "passive"))
      (node (ref "C31") (pin "1") (pinfunction "1_1") (pintype "passive"))
      (node (ref "C41") (pin "+") (pinfunction "+_+") (pintype "passive"))
      (node (ref "C42") (pin "1") (pinfunction "1_1") (pintype "passive"))
      (node (ref "C9") (pin "1") (pinfunction "1_1") (pintype "passive"))
      (node (ref "IC1") (pin "16") (pinfunction "VCC_16") (pintype "power_in"))
      (node (ref "IC2") (pin "4") (pinfunction "OUT_4") (pintype "passive"))
      (node (ref "J17") (pin "1") (pinfunction "VCC_1") (pintype "bidirectional"))
      (node (ref "R85") (pin "2") (pinfunction "2_2") (pintype "passive"))
      (node (ref "U1") (pin "1") (pinfunction "VCC_1") (pintype "power_in"))
      (node (ref "U10") (pin "1") (pinfunction "VCC_1") (pintype "power_in"))
      (node (ref "U11") (pin "8") (pinfunction "V+_8") (pintype "power_in"))
      (node (ref "U12") (pin "8") (pinfunction "V+_8") (pintype "power_in"))
      (node (ref "U17") (pin "8") (pinfunction "V+_8") (pintype "power_in"))
      (node (ref "U18") (pin "8") (pinfunction "V+_8") (pintype "power_in"))
      (node (ref "U19") (pin "8") (pinfunction "V+_8") (pintype "power_in"))
      (node (ref "U2") (pin "1") (pinfunction "VCC_1") (pintype "power_in"))
      (node (ref "U20") (pin "8") (pinfunction "V+_8") (pintype "power_in"))
      (node (ref "U21") (pin "1") (pinfunction "VDD_1_1") (pintype "power_in"))
      (node (ref "U21") (pin "24") (pinfunction "VDD_2_24") (pintype "power_in"))
      (node (ref "U21") (pin "48") (pinfunction "VDD_3_48") (pintype "power_in"))
      (node (ref "U21") (pin "9") (pinfunction "VDDA_9") (pintype "power_in"))
      (node (ref "U3") (pin "8") (pinfunction "V+_8") (pintype "power_in"))
      (node (ref "U4") (pin "8") (pinfunction "V+_8") (pintype "power_in"))
      (node (ref "U9") (pin "1") (pinfunction "VCC_1") (pintype "power_in"))
      (node (ref "VR1") (pin "3") (pinfunction "E_3") (pintype "passive"))
      (node (ref "VR2") (pin "3") (pinfunction "E_3") (pintype "passive"))
      (node (ref "VR3") (pin "3") (pinfunction "E_3") (pintype "passive"))
      (node (ref "VR4") (pin "3") (pinfunction "E_3") (pintype "passive"))
      (node (ref "VR5") (pin "3") (pinfunction "E_3") (pintype "passive"))
      (node (ref "VR6") (pin "3") (pinfunction "E_3") (pintype "passive"))
      (node (ref "VR7") (pin "3") (pinfunction "E_3") (pintype "passive"))
      (node (ref "VR8") (pin "3") (pinfunction "E_3") (pintype "passive"))
    )
    (net (code "2") (name "+5V") (class "Default")
      (node (ref "U13") (pin "1") (pinfunction "VDD_1") (pintype "bidirectional"))
      (node (ref "U13") (pin "9") (pinfunction "~{SHDN}_9") (pintype "bidirectional"))
      (node (ref "U14") (pin "1") (pinfunction "VDD_1") (pintype "bidirectional"))
      (node (ref "U14") (pin "9") (pinfunction "~{SHDN}_9") (pintype "bidirectional"))
      (node (ref "U5") (pin "1") (pinfunction "VDD_1") (pintype "bidirectional"))
      (node (ref "U5") (pin "9") (pinfunction "~{SHDN}_9") (pintype "bidirectional"))
      (node (ref "U6") (pin "1") (pinfunction "VDD_1") (pintype "bidirectional"))
      (node (ref "U6") (pin "9") (pinfunction "~{SHDN}_9") (pintype "bidirectional"))
    )
    (net (code "3") (name "+12V") (class "Default")
      (node (ref "C1") (pin "1") (pinfunction "1_1") (pintype "passive"))
      (node (ref "C3") (pin "1") (pinfunction "1_1") (pintype "passive"))
      (node (ref "C35") (pin "1") (pinfunction "1_1") (pintype "passive"))
      (node (ref "C37") (pin "+") (pinfunction "+_+") (pintype "passive"))
      (node (ref "C39") (pin "+") (pinfunction "+_+") (pintype "passive"))
      (node (ref "C5") (pin "1") (pinfunction "1_1") (pintype "passive"))
      (node (ref "C7") (pin "1") (pinfunction "1_1") (pintype "passive"))
      (node (ref "D1") (pin "C") (pinfunction "C_C") (pintype "passive"))
      (node (ref "IC2") (pin "3") (pinfunction "IN_3") (pintype "input"))
      (node (ref "U15") (pin "8") (pinfunction "V+_8") (pintype "power_in"))
      (node (ref "U16") (pin "8") (pinfunction "V+_8") (pintype "power_in"))
      (node (ref "U22") (pin "8") (pinfunction "V+_8") (pintype "power_in"))
      (node (ref "U7") (pin "8") (pinfunction "V+_8") (pintype "power_in"))
      (node (ref "U8") (pin "8") (pinfunction "V+_8") (pintype "power_in"))
    )
    (net (code "4") (name "-12V") (class "Default")
      (node (ref "C2") (pin "2") (pinfunction "2_2") (pintype "passive"))
      (node (ref "C34") (pin "2") (pinfunction "2_2") (pintype "passive"))
      (node (ref "C38") (pin "-") (pinfunction "-_-") (pintype "passive"))
      (node (ref "C4") (pin "2") (pinfunction "2_2") (pintype "passive"))
      (node (ref "C6") (pin "2") (pinfunction "2_2") (pintype "passive"))
      (node (ref "C8") (pin "2") (pinfunction "2_2") (pintype "passive"))
      (node (ref "D2") (pin "A") (pinfunction "A_A") (pintype "passive"))
      (node (ref "R90") (pin "2") (pinfunction "2_2") (pintype "passive"))
      (node (ref "U15") (pin "4") (pinfunction "V-_4") (pintype "power_in"))
      (node (ref "U16") (pin "4") (pinfunction "V-_4") (pintype "power_in"))
      (node (ref "U22") (pin "4") (pinfunction "V-_4") (pintype "power_in"))
      (node (ref "U7") (pin "4") (pinfunction "V-_4") (pintype "power_in"))
      (node (ref "U8") (pin "4") (pinfunction "V-_4") (pintype "power_in"))
    )
    (net (code "5") (name "1_IN_L") (class "Default")
      (node (ref "J1") (pin "P$1_TIP") (pinfunction "2_P$1_TIP") (pintype "passive"))
      (node (ref "R2") (pin "1") (pinfunction "1_1") (pintype "passive"))
    )
    (net (code "6") (name "1_IN_R") (class "Default")
      (node (ref "J2") (pin "P$1_TIP") (pinfunction "2_P$1_TIP") (pintype "passive"))
      (node (ref "R4") (pin "1") (pinfunction "1_1") (pintype "passive"))
    )
    (net (code "7") (name "2_IN_L") (class "Default")
      (node (ref "J3") (pin "P$1_TIP") (pinfunction "2_P$1_TIP") (pintype "passive"))
      (node (ref "R6") (pin "1") (pinfunction "1_1") (pintype "passive"))
    )
    (net (code "8") (name "2_IN_R") (class "Default")
      (node (ref "J4") (pin "P$1_TIP") (pinfunction "2_P$1_TIP") (pintype "passive"))
      (node (ref "R8") (pin "1") (pinfunction "1_1") (pintype "passive"))
    )
    (net (code "9") (name "3_IN_L") (class "Default")
      (node (ref "J5") (pin "P$1_TIP") (pinfunction "2_P$1_TIP") (pintype "passive"))
      (node (ref "R34") (pin "1") (pinfunction "1_1") (pintype "passive"))
    )
    (net (code "10") (name "3_IN_R") (class "Default")
      (node (ref "J6") (pin "P$1_TIP") (pinfunction "2_P$1_TIP") (pintype "passive"))
      (node (ref "R36") (pin "1") (pinfunction "1_1") (pintype "passive"))
    )
    (net (code "11") (name "4_IN_L") (class "Default")
      (node (ref "J7") (pin "P$1_TIP") (pinfunction "2_P$1_TIP") (pintype "passive"))
      (node (ref "R38") (pin "1") (pinfunction "1_1") (pintype "passive"))
    )
    (net (code "12") (name "4_IN_R") (class "Default")
      (node (ref "J8") (pin "P$1_TIP") (pinfunction "2_P$1_TIP") (pintype "passive"))
      (node (ref "R40") (pin "1") (pinfunction "1_1") (pintype "passive"))
    )
    (net (code "13") (name "AREF_-10") (class "Default")
      (node (ref "C40") (pin "1") (pinfunction "1_1") (pintype "passive"))
      (node (ref "D3") (pin "2") (pinfunction "A_2") (pintype "passive"))
      (node (ref "R1") (pin "1") (pinfunction "1_1") (pintype "passive"))
      (node (ref "R3") (pin "1") (pinfunction "1_1") (pintype "passive"))
      (node (ref "R33") (pin "1") (pinfunction "1_1") (pintype "passive"))
      (node (ref "R35") (pin "1") (pinfunction "1_1") (pintype "passive"))
      (node (ref "R37") (pin "1") (pinfunction "1_1") (pintype "passive"))
      (node (ref "R39") (pin "1") (pinfunction "1_1") (pintype "passive"))
      (node (ref "R5") (pin "1") (pinfunction "1_1") (pintype "passive"))
      (node (ref "R65") (pin "1") (pinfunction "1_1") (pintype "passive"))
      (node (ref "R67") (pin "1") (pinfunction "1_1") (pintype "passive"))
      (node (ref "R69") (pin "1") (pinfunction "1_1") (pintype "passive"))
      (node (ref "R7") (pin "1") (pinfunction "1_1") (pintype "passive"))
      (node (ref "R71") (pin "1") (pinfunction "1_1") (pintype "passive"))
      (node (ref "R90") (pin "1") (pinfunction "1_1") (pintype "passive"))
    )
    (net (code "14") (name "AUX_IN_L") (class "Default")
      (node (ref "JP1") (pin "1") (pinfunction "1_1") (pintype "passive"))
      (node (ref "R86") (pin "1") (pinfunction "1_1") (pintype "passive"))
    )
    (net (code "15") (name "AUX_IN_R") (class "Default")
      (node (ref "JP1") (pin "2") (pinfunction "2_2") (pintype "passive"))
      (node (ref "R87") (pin "1") (pinfunction "1_1") (pintype "passive"))
    )
    (net (code "16") (name "BIAS_DAC1_L") (class "Default")
      (node (ref "R16") (pin "1") (pinfunction "1_1") (pintype "passive"))
      (node (ref "U1") (pin "8") (pinfunction "VOUTA_8") (pintype "output"))
    )
    (net (code "17") (name "BIAS_DAC1_R") (class "Default")
      (node (ref "R15") (pin "1") (pinfunction "1_1") (pintype "passive"))
      (node (ref "U1") (pin "6") (pinfunction "VOUTB_6") (pintype "output"))
    )
    (net (code "18") (name "BIAS_DAC2_L") (class "Default")
      (node (ref "R20") (pin "1") (pinfunction "1_1") (pintype "passive"))
      (node (ref "U2") (pin "8") (pinfunction "VOUTA_8") (pintype "output"))
    )
    (net (code "19") (name "BIAS_DAC2_R") (class "Default")
      (node (ref "R19") (pin "1") (pinfunction "1_1") (pintype "passive"))
      (node (ref "U2") (pin "6") (pinfunction "VOUTB_6") (pintype "output"))
    )
    (net (code "20") (name "BIAS_DAC3_L") (class "Default")
      (node (ref "R51") (pin "1") (pinfunction "1_1") (pintype "passive"))
      (node (ref "U9") (pin "8") (pinfunction "VOUTA_8") (pintype "output"))
    )
    (net (code "21") (name "BIAS_DAC3_R") (class "Default")
      (node (ref "R47") (pin "1") (pinfunction "1_1") (pintype "passive"))
      (node (ref "U9") (pin "6") (pinfunction "VOUTB_6") (pintype "output"))
    )
    (net (code "22") (name "BIAS_DAC4_L") (class "Default")
      (node (ref "R52") (pin "1") (pinfunction "1_1") (pintype "passive"))
      (node (ref "U10") (pin "8") (pinfunction "VOUTA_8") (pintype "output"))
    )
    (net (code "23") (name "BIAS_DAC4_R") (class "Default")
      (node (ref "R50") (pin "1") (pinfunction "1_1") (pintype "passive"))
      (node (ref "U10") (pin "6") (pinfunction "VOUTB_6") (pintype "output"))
    )
    (net (code "24") (name "CS_BIAS_DAC_1") (class "Default")
      (node (ref "U1") (pin "2") (pinfunction "CS_2") (pintype "input"))
      (node (ref "U21") (pin "45") (pinfunction "PB8/I2C1_SCL/TIM16_CH1_45") (pintype "power_in"))
    )
    (net (code "25") (name "CS_BIAS_DAC_2") (class "Default")
      (node (ref "U2") (pin "2") (pinfunction "CS_2") (pintype "input"))
      (node (ref "U21") (pin "46") (pinfunction "PB9/I2C1_SDA/IR_OUT/SPI2_NSS/TIM17_CH1/EVENTOUT_46") (pintype "power_in"))
    )
    (net (code "26") (name "CS_BIAS_DAC_3") (class "Default")
      (node (ref "U21") (pin "21") (pinfunction "PB10/I2C2_SCL_21") (pintype "bidirectional"))
      (node (ref "U9") (pin "2") (pinfunction "CS_2") (pintype "input"))
    )
    (net (code "27") (name "CS_BIAS_DAC_4") (class "Default")
      (node (ref "U10") (pin "2") (pinfunction "CS_2") (pintype "input"))
      (node (ref "U21") (pin "22") (pinfunction "PB11/I2C2_SDA/EVENTOUT_22") (pintype "bidirectional"))
    )
    (net (code "28") (name "CS_DAC_1") (class "Default")
      (node (ref "U21") (pin "29") (pinfunction "PA8/USART1_CK/TIM1_CH1/EVENTOUT/MCO_29") (pintype "bidirectional"))
      (node (ref "U5") (pin "3") (pinfunction "~{CS}_3") (pintype "bidirectional"))
    )
    (net (code "29") (name "CS_DAC_2") (class "Default")
      (node (ref "U21") (pin "30") (pinfunction "PA9/USART1_TX/TIM1_CH2/TIM15_BKIN_30") (pintype "bidirectional"))
      (node (ref "U6") (pin "3") (pinfunction "~{CS}_3") (pintype "bidirectional"))
    )
    (net (code "30") (name "CS_DAC_3") (class "Default")
      (node (ref "U13") (pin "3") (pinfunction "~{CS}_3") (pintype "bidirectional"))
      (node (ref "U21") (pin "31") (pinfunction "PA10/USART1_RX/TIM1_CH3/TIM17_BKIN_31") (pintype "bidirectional"))
    )
    (net (code "31") (name "CS_DAC_4") (class "Default")
      (node (ref "U14") (pin "3") (pinfunction "~{CS}_3") (pintype "bidirectional"))
      (node (ref "U21") (pin "32") (pinfunction "PA11/USART1_CTS/TIM1_CH4/EVENTOUT_32") (pintype "bidirectional"))
    )
    (net (code "32") (name "GND") (class "Default")
      (node (ref "C1") (pin "2") (pinfunction "2_2") (pintype "passive"))
      (node (ref "C10") (pin "2") (pinfunction "2_2") (pintype "passive"))
      (node (ref "C11") (pin "2") (pinfunction "2_2") (pintype "passive"))
      (node (ref "C12") (pin "2") (pinfunction "2_2") (pintype "passive"))
      (node (ref "C13") (pin "2") (pinfunction "2_2") (pintype "passive"))
      (node (ref "C14") (pin "2") (pinfunction "2_2") (pintype "passive"))
      (node (ref "C15") (pin "2") (pinfunction "2_2") (pintype "passive"))
      (node (ref "C16") (pin "2") (pinfunction "2_2") (pintype "passive"))
      (node (ref "C17") (pin "2") (pinfunction "2_2") (pintype "passive"))
      (node (ref "C18") (pin "2") (pinfunction "2_2") (pintype "passive"))
      (node (ref "C2") (pin "1") (pinfunction "1_1") (pintype "passive"))
      (node (ref "C23") (pin "2") (pinfunction "2_2") (pintype "passive"))
      (node (ref "C24") (pin "2") (pinfunction "2_2") (pintype "passive"))
      (node (ref "C25") (pin "2") (pinfunction "2_2") (pintype "passive"))
      (node (ref "C26") (pin "1") (pinfunction "1_1") (pintype "passive"))
      (node (ref "C27") (pin "1") (pinfunction "1_1") (pintype "passive"))
      (node (ref "C28") (pin "2") (pinfunction "2_2") (pintype "passive"))
      (node (ref "C29") (pin "2") (pinfunction "2_2") (pintype "passive"))
      (node (ref "C3") (pin "2") (pinfunction "2_2") (pintype "passive"))
      (node (ref "C30") (pin "2") (pinfunction "2_2") (pintype "passive"))
      (node (ref "C31") (pin "2") (pinfunction "2_2") (pintype "passive"))
      (node (ref "C34") (pin "1") (pinfunction "1_1") (pintype "passive"))
      (node (ref "C35") (pin "2") (pinfunction "2_2") (pintype "passive"))
      (node (ref "C36") (pin "GND1") (pinfunction "GND_GND1") (pintype "bidirectional"))
      (node (ref "C36") (pin "GND2") (pinfunction "GND_GND2") (pintype "bidirectional"))
      (node (ref "C36") (pin "GND3") (pinfunction "GND_GND3") (pintype "bidirectional"))
      (node (ref "C36") (pin "GND4") (pinfunction "GND_GND4") (pintype "bidirectional"))
      (node (ref "C36") (pin "GND5") (pinfunction "GND_GND5") (pintype "bidirectional"))
      (node (ref "C36") (pin "GND6") (pinfunction "GND_GND6") (pintype "bidirectional"))
      (node (ref "C37") (pin "-") (pinfunction "-_-") (pintype "passive"))
      (node (ref "C38") (pin "+") (pinfunction "+_+") (pintype "passive"))
      (node (ref "C39") (pin "-") (pinfunction "-_-") (pintype "passive"))
      (node (ref "C4") (pin "1") (pinfunction "1_1") (pintype "passive"))
      (node (ref "C40") (pin "2") (pinfunction "2_2") (pintype "passive"))
      (node (ref "C41") (pin "-") (pinfunction "-_-") (pintype "passive"))
      (node (ref "C42") (pin "2") (pinfunction "2_2") (pintype "passive"))
      (node (ref "C5") (pin "2") (pinfunction "2_2") (pintype "passive"))
      (node (ref "C6") (pin "1") (pinfunction "1_1") (pintype "passive"))
      (node (ref "C7") (pin "2") (pinfunction "2_2") (pintype "passive"))
      (node (ref "C8") (pin "1") (pinfunction "1_1") (pintype "passive"))
      (node (ref "C9") (pin "2") (pinfunction "2_2") (pintype "passive"))
      (node (ref "D3") (pin "1") (pinfunction "C_1") (pintype "passive"))
      (node (ref "IC1") (pin "6") (pinfunction "INH_6") (pintype "input"))
      (node (ref "IC1") (pin "7") (pinfunction "VEE_7") (pintype "power_in"))
      (node (ref "IC1") (pin "8") (pinfunction "GND_8") (pintype "power_in"))
      (node (ref "IC2") (pin "1") (pinfunction "ADJ_1") (pintype "input"))
      (node (ref "J1") (pin "P$3_SLEEVE") (pinfunction "1_P$3_SLEEVE") (pintype "passive"))
      (node (ref "J10") (pin "P$3_SLEEVE") (pinfunction "1_P$3_SLEEVE") (pintype "passive"))
      (node (ref "J11") (pin "P$3_SLEEVE") (pinfunction "1_P$3_SLEEVE") (pintype "passive"))
      (node (ref "J12") (pin "P$3_SLEEVE") (pinfunction "1_P$3_SLEEVE") (pintype "passive"))
      (node (ref "J13") (pin "P$3_SLEEVE") (pinfunction "1_P$3_SLEEVE") (pintype "passive"))
      (node (ref "J14") (pin "P$3_SLEEVE") (pinfunction "1_P$3_SLEEVE") (pintype "passive"))
      (node (ref "J15") (pin "P$3_SLEEVE") (pinfunction "1_P$3_SLEEVE") (pintype "passive"))
      (node (ref "J16") (pin "P$3_SLEEVE") (pinfunction "1_P$3_SLEEVE") (pintype "passive"))
      (node (ref "J17") (pin "3") (pinfunction "GND_3") (pintype "bidirectional"))
      (node (ref "J17") (pin "5") (pinfunction "GND_5") (pintype "bidirectional"))
      (node (ref "J17") (pin "9") (pinfunction "GNDDTCT_9") (pintype "bidirectional"))
      (node (ref "J18") (pin "P$3_SLEEVE") (pinfunction "1_P$3_SLEEVE") (pintype "passive"))
      (node (ref "J19") (pin "P$3_SLEEVE") (pinfunction "1_P$3_SLEEVE") (pintype "passive"))
      (node (ref "J2") (pin "P$3_SLEEVE") (pinfunction "1_P$3_SLEEVE") (pintype "passive"))
      (node (ref "J3") (pin "P$3_SLEEVE") (pinfunction "1_P$3_SLEEVE") (pintype "passive"))
      (node (ref "J4") (pin "P$3_SLEEVE") (pinfunction "1_P$3_SLEEVE") (pintype "passive"))
      (node (ref "J5") (pin "P$3_SLEEVE") (pinfunction "1_P$3_SLEEVE") (pintype "passive"))
      (node (ref "J6") (pin "P$3_SLEEVE") (pinfunction "1_P$3_SLEEVE") (pintype "passive"))
      (node (ref "J7") (pin "P$3_SLEEVE") (pinfunction "1_P$3_SLEEVE") (pintype "passive"))
      (node (ref "J8") (pin "P$3_SLEEVE") (pinfunction "1_P$3_SLEEVE") (pintype "passive"))
      (node (ref "J9") (pin "P$3_SLEEVE") (pinfunction "1_P$3_SLEEVE") (pintype "passive"))
      (node (ref "JP1") (pin "3") (pinfunction "3_3") (pintype "passive"))
      (node (ref "JP2") (pin "3") (pinfunction "3_3") (pintype "passive"))
      (node (ref "R21") (pin "1") (pinfunction "1_1") (pintype "passive"))
      (node (ref "R22") (pin "2") (pinfunction "2_2") (pintype "passive"))
      (node (ref "R24") (pin "2") (pinfunction "2_2") (pintype "passive"))
      (node (ref "R27") (pin "2") (pinfunction "2_2") (pintype "passive"))
      (node (ref "R53") (pin "1") (pinfunction "1_1") (pintype "passive"))
      (node (ref "R54") (pin "1") (pinfunction "1_1") (pintype "passive"))
      (node (ref "R55") (pin "1") (pinfunction "1_1") (pintype "passive"))
      (node (ref "R56") (pin "1") (pinfunction "1_1") (pintype "passive"))
      (node (ref "R81") (pin "1") (pinfunction "1_1") (pintype "passive"))
      (node (ref "R82") (pin "1") (pinfunction "1_1") (pintype "passive"))
      (node (ref "R83") (pin "1") (pinfunction "1_1") (pintype "passive"))
      (node (ref "R84") (pin "1") (pinfunction "1_1") (pintype "passive"))
      (node (ref "U1") (pin "5") (pinfunction "LDAC_5") (pintype "input"))
      (node (ref "U1") (pin "7") (pinfunction "GND_7") (pintype "power_in"))
      (node (ref "U10") (pin "5") (pinfunction "LDAC_5") (pintype "input"))
      (node (ref "U10") (pin "7") (pinfunction "GND_7") (pintype "power_in"))
      (node (ref "U11") (pin "3") (pinfunction "+IN_3") (pintype "input"))
      (node (ref "U11") (pin "4") (pinfunction "V-_4") (pintype "power_in"))
      (node (ref "U11") (pin "5") (pinfunction "+IN_5") (pintype "input"))
      (node (ref "U12") (pin "3") (pinfunction "+IN_3") (pintype "input"))
      (node (ref "U12") (pin "4") (pinfunction "V-_4") (pintype "power_in"))
      (node (ref "U12") (pin "5") (pinfunction "+IN_5") (pintype "input"))
      (node (ref "U13") (pin "12") (pinfunction "VSS_12") (pintype "bidirectional"))
      (node (ref "U13") (pin "8") (pinfunction "~{LDAC}_8") (pintype "bidirectional"))
      (node (ref "U14") (pin "12") (pinfunction "VSS_12") (pintype "bidirectional"))
      (node (ref "U14") (pin "8") (pinfunction "~{LDAC}_8") (pintype "bidirectional"))
      (node (ref "U17") (pin "3") (pinfunction "+IN_3") (pintype "input"))
      (node (ref "U17") (pin "4") (pinfunction "V-_4") (pintype "power_in"))
      (node (ref "U18") (pin "3") (pinfunction "+IN_3") (pintype "input"))
      (node (ref "U18") (pin "4") (pinfunction "V-_4") (pintype "power_in"))
      (node (ref "U19") (pin "3") (pinfunction "+IN_3") (pintype "input"))
      (node (ref "U19") (pin "4") (pinfunction "V-_4") (pintype "power_in"))
      (node (ref "U2") (pin "5") (pinfunction "LDAC_5") (pintype "input"))
      (node (ref "U2") (pin "7") (pinfunction "GND_7") (pintype "power_in"))
      (node (ref "U20") (pin "3") (pinfunction "+IN_3") (pintype "input"))
      (node (ref "U20") (pin "4") (pinfunction "V-_4") (pintype "power_in"))
      (node (ref "U21") (pin "23") (pinfunction "VSS_1_23") (pintype "power_in"))
      (node (ref "U21") (pin "44") (pinfunction "BOOT0_44") (pintype "bidirectional"))
      (node (ref "U21") (pin "47") (pinfunction "VSS_2_47") (pintype "power_in"))
      (node (ref "U21") (pin "8") (pinfunction "VSSA_8") (pintype "power_in"))
      (node (ref "U22") (pin "3") (pinfunction "+IN_3") (pintype "input"))
      (node (ref "U22") (pin "5") (pinfunction "+IN_5") (pintype "input"))
      (node (ref "U3") (pin "3") (pinfunction "+IN_3") (pintype "input"))
      (node (ref "U3") (pin "4") (pinfunction "V-_4") (pintype "power_in"))
      (node (ref "U3") (pin "5") (pinfunction "+IN_5") (pintype "input"))
      (node (ref "U4") (pin "3") (pinfunction "+IN_3") (pintype "input"))
      (node (ref "U4") (pin "4") (pinfunction "V-_4") (pintype "power_in"))
      (node (ref "U4") (pin "5") (pinfunction "+IN_5") (pintype "input"))
      (node (ref "U5") (pin "12") (pinfunction "VSS_12") (pintype "bidirectional"))
      (node (ref "U5") (pin "8") (pinfunction "~{LDAC}_8") (pintype "bidirectional"))
      (node (ref "U6") (pin "12") (pinfunction "VSS_12") (pintype "bidirectional"))
      (node (ref "U6") (pin "8") (pinfunction "~{LDAC}_8") (pintype "bidirectional"))
      (node (ref "U9") (pin "5") (pinfunction "LDAC_5") (pintype "input"))
      (node (ref "U9") (pin "7") (pinfunction "GND_7") (pintype "power_in"))
      (node (ref "VR1") (pin "1") (pinfunction "A_1") (pintype "passive"))
      (node (ref "VR2") (pin "1") (pinfunction "A_1") (pintype "passive"))
      (node (ref "VR3") (pin "1") (pinfunction "A_1") (pintype "passive"))
      (node (ref "VR4") (pin "1") (pinfunction "A_1") (pintype "passive"))
      (node (ref "VR5") (pin "1") (pinfunction "A_1") (pintype "passive"))
      (node (ref "VR6") (pin "1") (pinfunction "A_1") (pintype "passive"))
      (node (ref "VR7") (pin "1") (pinfunction "A_1") (pintype "passive"))
      (node (ref "VR8") (pin "1") (pinfunction "A_1") (pintype "passive"))
    )
    (net (code "33") (name "MISO") (class "Default")
      (node (ref "U21") (pin "40") (pinfunction "PB4/SPI1_MISO/TIM3_CH1/EVENTOUT_40") (pintype "bidirectional"))
    )
    (net (code "34") (name "MOSI") (class "Default")
      (node (ref "U1") (pin "4") (pinfunction "SDI_4") (pintype "input"))
      (node (ref "U10") (pin "4") (pinfunction "SDI_4") (pintype "input"))
      (node (ref "U13") (pin "5") (pinfunction "SDI_5") (pintype "bidirectional"))
      (node (ref "U14") (pin "5") (pinfunction "SDI_5") (pintype "bidirectional"))
      (node (ref "U2") (pin "4") (pinfunction "SDI_4") (pintype "input"))
      (node (ref "U21") (pin "41") (pinfunction "PB5/SPI1_MOSI/I2C1_SMBA/TIM16_BKIN/TIM3_CH2_41") (pintype "bidirectional"))
      (node (ref "U5") (pin "5") (pinfunction "SDI_5") (pintype "bidirectional"))
      (node (ref "U6") (pin "5") (pinfunction "SDI_5") (pintype "bidirectional"))
      (node (ref "U9") (pin "4") (pinfunction "SDI_4") (pintype "input"))
    )
    (net (code "35") (name "MUX_ADDR_0") (class "Default")
      (node (ref "IC1") (pin "11") (pinfunction "A_11") (pintype "input"))
      (node (ref "U21") (pin "25") (pinfunction "PB12/SPI2_NSS/TIM1_BKIN/EVENTOUT_25") (pintype "bidirectional"))
    )
    (net (code "36") (name "MUX_ADDR_1") (class "Default")
      (node (ref "IC1") (pin "10") (pinfunction "B_10") (pintype "input"))
      (node (ref "U21") (pin "26") (pinfunction "PB13/SPI2_SCK/TIM1_CH1N_26") (pintype "bidirectional"))
    )
    (net (code "37") (name "MUX_ADDR_2") (class "Default")
      (node (ref "IC1") (pin "9") (pinfunction "C_9") (pintype "input"))
      (node (ref "U21") (pin "27") (pinfunction "PB14/SPI2_MISO/TIM1_CH2N/TIM15_CH1_27") (pintype "bidirectional"))
    )
    (net (code "38") (name "NRST") (class "Default")
      (node (ref "J17") (pin "10") (pinfunction "~{RESET}_10") (pintype "bidirectional"))
      (node (ref "R85") (pin "1") (pinfunction "1_1") (pintype "passive"))
      (node (ref "U21") (pin "7") (pinfunction "NRST_7") (pintype "bidirectional"))
    )
    (net (code "39") (name "Net-(C36-+12V-PadPOS1)") (class "Default")
      (node (ref "C36") (pin "POS1") (pinfunction "+12V_POS1") (pintype "bidirectional"))
      (node (ref "C36") (pin "POS2") (pinfunction "+12V_POS2") (pintype "bidirectional"))
      (node (ref "D1") (pin "A") (pinfunction "A_A") (pintype "passive"))
    )
    (net (code "40") (name "Net-(C36--12V-PadNEG1)") (class "Default")
      (node (ref "C36") (pin "NEG1") (pinfunction "-12V_NEG1") (pintype "bidirectional"))
      (node (ref "C36") (pin "NEG2") (pinfunction "-12V_NEG2") (pintype "bidirectional"))
      (node (ref "D2") (pin "C") (pinfunction "C_C") (pintype "passive"))
    )
    (net (code "41") (name "Net-(J9-2)") (class "Default")
      (node (ref "J9") (pin "P$1_TIP") (pinfunction "2_P$1_TIP") (pintype "passive"))
      (node (ref "R66") (pin "1") (pinfunction "1_1") (pintype "passive"))
    )
    (net (code "42") (name "Net-(J10-2)") (class "Default")
      (node (ref "J10") (pin "P$1_TIP") (pinfunction "2_P$1_TIP") (pintype "passive"))
      (node (ref "R68") (pin "1") (pinfunction "1_1") (pintype "passive"))
    )
    (net (code "43") (name "Net-(J11-2)") (class "Default")
      (node (ref "J11") (pin "P$1_TIP") (pinfunction "2_P$1_TIP") (pintype "passive"))
      (node (ref "R70") (pin "1") (pinfunction "1_1") (pintype "passive"))
    )
    (net (code "44") (name "Net-(J12-2)") (class "Default")
      (node (ref "J12") (pin "P$1_TIP") (pinfunction "2_P$1_TIP") (pintype "passive"))
      (node (ref "R72") (pin "1") (pinfunction "1_1") (pintype "passive"))
    )
    (net (code "45") (name "Net-(J13-2)") (class "Default")
      (node (ref "J13") (pin "P$1_TIP") (pinfunction "2_P$1_TIP") (pintype "passive"))
      (node (ref "R77") (pin "2") (pinfunction "2_2") (pintype "passive"))
    )
    (net (code "46") (name "Net-(J14-2)") (class "Default")
      (node (ref "J14") (pin "P$1_TIP") (pinfunction "2_P$1_TIP") (pintype "passive"))
      (node (ref "R78") (pin "2") (pinfunction "2_2") (pintype "passive"))
    )
    (net (code "47") (name "Net-(J15-2)") (class "Default")
      (node (ref "J15") (pin "P$1_TIP") (pinfunction "2_P$1_TIP") (pintype "passive"))
      (node (ref "R79") (pin "2") (pinfunction "2_2") (pintype "passive"))
    )
    (net (code "48") (name "Net-(J16-2)") (class "Default")
      (node (ref "J16") (pin "P$1_TIP") (pinfunction "2_P$1_TIP") (pintype "passive"))
      (node (ref "R80") (pin "2") (pinfunction "2_2") (pintype "passive"))
    )
    (net (code "49") (name "Net-(U3A--IN)") (class "Default")
      (node (ref "R1") (pin "2") (pinfunction "2_2") (pintype "passive"))
      (node (ref "R2") (pin "2") (pinfunction "2_2") (pintype "passive"))
      (node (ref "R9") (pin "1") (pinfunction "1_1") (pintype "passive"))
      (node (ref "U3") (pin "2") (pinfunction "-IN_2") (pintype "input"))
    )
    (net (code "50") (name "Net-(U3A-OUT)") (class "Default")
      (node (ref "R9") (pin "2") (pinfunction "2_2") (pintype "passive"))
      (node (ref "U3") (pin "1") (pinfunction "OUT_1") (pintype "output"))
      (node (ref "U5") (pin "13") (pinfunction "VREFA_13") (pintype "bidirectional"))
    )
    (net (code "51") (name "Net-(U3B--IN)") (class "Default")
      (node (ref "R10") (pin "1") (pinfunction "1_1") (pintype "passive"))
      (node (ref "R3") (pin "2") (pinfunction "2_2") (pintype "passive"))
      (node (ref "R4") (pin "2") (pinfunction "2_2") (pintype "passive"))
      (node (ref "U3") (pin "6") (pinfunction "-IN_6") (pintype "input"))
    )
    (net (code "52") (name "Net-(U3B-OUT)") (class "Default")
      (node (ref "R10") (pin "2") (pinfunction "2_2") (pintype "passive"))
      (node (ref "U3") (pin "7") (pinfunction "OUT_7") (pintype "output"))
      (node (ref "U5") (pin "11") (pinfunction "VREFB_11") (pintype "bidirectional"))
    )
    (net (code "53") (name "Net-(U4A--IN)") (class "Default")
      (node (ref "R11") (pin "1") (pinfunction "1_1") (pintype "passive"))
      (node (ref "R5") (pin "2") (pinfunction "2_2") (pintype "passive"))
      (node (ref "R6") (pin "2") (pinfunction "2_2") (pintype "passive"))
      (node (ref "U4") (pin "2") (pinfunction "-IN_2") (pintype "input"))
    )
    (net (code "54") (name "Net-(U4A-OUT)") (class "Default")
      (node (ref "R11") (pin "2") (pinfunction "2_2") (pintype "passive"))
      (node (ref "U4") (pin "1") (pinfunction "OUT_1") (pintype "output"))
      (node (ref "U6") (pin "13") (pinfunction "VREFA_13") (pintype "bidirectional"))
    )
    (net (code "55") (name "Net-(U4B--IN)") (class "Default")
      (node (ref "R12") (pin "1") (pinfunction "1_1") (pintype "passive"))
      (node (ref "R7") (pin "2") (pinfunction "2_2") (pintype "passive"))
      (node (ref "R8") (pin "2") (pinfunction "2_2") (pintype "passive"))
      (node (ref "U4") (pin "6") (pinfunction "-IN_6") (pintype "input"))
    )
    (net (code "56") (name "Net-(U4B-OUT)") (class "Default")
      (node (ref "R12") (pin "2") (pinfunction "2_2") (pintype "passive"))
      (node (ref "U4") (pin "7") (pinfunction "OUT_7") (pintype "output"))
      (node (ref "U6") (pin "11") (pinfunction "VREFB_11") (pintype "bidirectional"))
    )
    (net (code "57") (name "Net-(U5-VOUT_A)") (class "Default")
      (node (ref "R13") (pin "1") (pinfunction "1_1") (pintype "passive"))
      (node (ref "U5") (pin "14") (pinfunction "VOUT_A_14") (pintype "bidirectional"))
    )
    (net (code "58") (name "Net-(U5-VOUT_B)") (class "Default")
      (node (ref "R14") (pin "1") (pinfunction "1_1") (pintype "passive"))
      (node (ref "U5") (pin "10") (pinfunction "VOUT_B_10") (pintype "bidirectional"))
    )
    (net (code "59") (name "Net-(U6-VOUT_A)") (class "Default")
      (node (ref "R17") (pin "1") (pinfunction "1_1") (pintype "passive"))
      (node (ref "U6") (pin "14") (pinfunction "VOUT_A_14") (pintype "bidirectional"))
    )
    (net (code "60") (name "Net-(U6-VOUT_B)") (class "Default")
      (node (ref "R18") (pin "1") (pinfunction "1_1") (pintype "passive"))
      (node (ref "U6") (pin "10") (pinfunction "VOUT_B_10") (pintype "bidirectional"))
    )
    (net (code "61") (name "Net-(U7A-+IN)") (class "Default")
      (node (ref "R16") (pin "2") (pinfunction "2_2") (pintype "passive"))
      (node (ref "R24") (pin "1") (pinfunction "1_1") (pintype "passive"))
      (node (ref "U7") (pin "3") (pinfunction "+IN_3") (pintype "input"))
    )
    (net (code "62") (name "Net-(U7A--IN)") (class "Default")
      (node (ref "R13") (pin "2") (pinfunction "2_2") (pintype "passive"))
      (node (ref "R23") (pin "1") (pinfunction "1_1") (pintype "passive"))
      (node (ref "U7") (pin "2") (pinfunction "-IN_2") (pintype "input"))
    )
    (net (code "63") (name "Net-(U7A-OUT)") (class "Default")
      (node (ref "R23") (pin "2") (pinfunction "2_2") (pintype "passive"))
      (node (ref "R29") (pin "1") (pinfunction "1_1") (pintype "passive"))
      (node (ref "U7") (pin "1") (pinfunction "OUT_1") (pintype "output"))
    )
    (net (code "64") (name "Net-(U7B-+IN)") (class "Default")
      (node (ref "R15") (pin "2") (pinfunction "2_2") (pintype "passive"))
      (node (ref "R21") (pin "2") (pinfunction "2_2") (pintype "passive"))
      (node (ref "U7") (pin "5") (pinfunction "+IN_5") (pintype "input"))
    )
    (net (code "65") (name "Net-(U7B--IN)") (class "Default")
      (node (ref "R14") (pin "2") (pinfunction "2_2") (pintype "passive"))
      (node (ref "R25") (pin "1") (pinfunction "1_1") (pintype "passive"))
      (node (ref "U7") (pin "6") (pinfunction "-IN_6") (pintype "input"))
    )
    (net (code "66") (name "Net-(U7B-OUT)") (class "Default")
      (node (ref "R25") (pin "2") (pinfunction "2_2") (pintype "passive"))
      (node (ref "R30") (pin "1") (pinfunction "1_1") (pintype "passive"))
      (node (ref "U7") (pin "7") (pinfunction "OUT_7") (pintype "output"))
    )
    (net (code "67") (name "Net-(U8A-+IN)") (class "Default")
      (node (ref "R20") (pin "2") (pinfunction "2_2") (pintype "passive"))
      (node (ref "R27") (pin "1") (pinfunction "1_1") (pintype "passive"))
      (node (ref "U8") (pin "3") (pinfunction "+IN_3") (pintype "input"))
    )
    (net (code "68") (name "Net-(U8A--IN)") (class "Default")
      (node (ref "R17") (pin "2") (pinfunction "2_2") (pintype "passive"))
      (node (ref "R26") (pin "1") (pinfunction "1_1") (pintype "passive"))
      (node (ref "U8") (pin "2") (pinfunction "-IN_2") (pintype "input"))
    )
    (net (code "69") (name "Net-(U8A-OUT)") (class "Default")
      (node (ref "R26") (pin "2") (pinfunction "2_2") (pintype "passive"))
      (node (ref "R31") (pin "1") (pinfunction "1_1") (pintype "passive"))
      (node (ref "U8") (pin "1") (pinfunction "OUT_1") (pintype "output"))
    )
    (net (code "70") (name "Net-(U8B-+IN)") (class "Default")
      (node (ref "R19") (pin "2") (pinfunction "2_2") (pintype "passive"))
      (node (ref "R22") (pin "1") (pinfunction "1_1") (pintype "passive"))
      (node (ref "U8") (pin "5") (pinfunction "+IN_5") (pintype "input"))
    )
    (net (code "71") (name "Net-(U8B--IN)") (class "Default")
      (node (ref "R18") (pin "2") (pinfunction "2_2") (pintype "passive"))
      (node (ref "R28") (pin "1") (pinfunction "1_1") (pintype "passive"))
      (node (ref "U8") (pin "6") (pinfunction "-IN_6") (pintype "input"))
    )
    (net (code "72") (name "Net-(U8B-OUT)") (class "Default")
      (node (ref "R28") (pin "2") (pinfunction "2_2") (pintype "passive"))
      (node (ref "R32") (pin "1") (pinfunction "1_1") (pintype "passive"))
      (node (ref "U8") (pin "7") (pinfunction "OUT_7") (pintype "output"))
    )
    (net (code "73") (name "Net-(U11A--IN)") (class "Default")
      (node (ref "R33") (pin "2") (pinfunction "2_2") (pintype "passive"))
      (node (ref "R34") (pin "2") (pinfunction "2_2") (pintype "passive"))
      (node (ref "R41") (pin "1") (pinfunction "1_1") (pintype "passive"))
      (node (ref "U11") (pin "2") (pinfunction "-IN_2") (pintype "input"))
    )
    (net (code "74") (name "Net-(U11A-OUT)") (class "Default")
      (node (ref "R41") (pin "2") (pinfunction "2_2") (pintype "passive"))
      (node (ref "U11") (pin "1") (pinfunction "OUT_1") (pintype "output"))
      (node (ref "U13") (pin "13") (pinfunction "VREFA_13") (pintype "bidirectional"))
    )
    (net (code "75") (name "Net-(U11B--IN)") (class "Default")
      (node (ref "R35") (pin "2") (pinfunction "2_2") (pintype "passive"))
      (node (ref "R36") (pin "2") (pinfunction "2_2") (pintype "passive"))
      (node (ref "R42") (pin "1") (pinfunction "1_1") (pintype "passive"))
      (node (ref "U11") (pin "6") (pinfunction "-IN_6") (pintype "input"))
    )
    (net (code "76") (name "Net-(U11B-OUT)") (class "Default")
      (node (ref "R42") (pin "2") (pinfunction "2_2") (pintype "passive"))
      (node (ref "U11") (pin "7") (pinfunction "OUT_7") (pintype "output"))
      (node (ref "U13") (pin "11") (pinfunction "VREFB_11") (pintype "bidirectional"))
    )
    (net (code "77") (name "Net-(U12A--IN)") (class "Default")
      (node (ref "R37") (pin "2") (pinfunction "2_2") (pintype "passive"))
      (node (ref "R38") (pin "2") (pinfunction "2_2") (pintype "passive"))
      (node (ref "R43") (pin "1") (pinfunction "1_1") (pintype "passive"))
      (node (ref "U12") (pin "2") (pinfunction "-IN_2") (pintype "input"))
    )
    (net (code "78") (name "Net-(U12A-OUT)") (class "Default")
      (node (ref "R43") (pin "2") (pinfunction "2_2") (pintype "passive"))
      (node (ref "U12") (pin "1") (pinfunction "OUT_1") (pintype "output"))
      (node (ref "U14") (pin "13") (pinfunction "VREFA_13") (pintype "bidirectional"))
    )
    (net (code "79") (name "Net-(U12B--IN)") (class "Default")
      (node (ref "R39") (pin "2") (pinfunction "2_2") (pintype "passive"))
      (node (ref "R40") (pin "2") (pinfunction "2_2") (pintype "passive"))
      (node (ref "R44") (pin "1") (pinfunction "1_1") (pintype "passive"))
      (node (ref "U12") (pin "6") (pinfunction "-IN_6") (pintype "input"))
    )
    (net (code "80") (name "Net-(U12B-OUT)") (class "Default")
      (node (ref "R44") (pin "2") (pinfunction "2_2") (pintype "passive"))
      (node (ref "U12") (pin "7") (pinfunction "OUT_7") (pintype "output"))
      (node (ref "U14") (pin "11") (pinfunction "VREFB_11") (pintype "bidirectional"))
    )
    (net (code "81") (name "Net-(U13-VOUT_A)") (class "Default")
      (node (ref "R45") (pin "1") (pinfunction "1_1") (pintype "passive"))
      (node (ref "U13") (pin "14") (pinfunction "VOUT_A_14") (pintype "bidirectional"))
    )
    (net (code "82") (name "Net-(U13-VOUT_B)") (class "Default")
      (node (ref "R46") (pin "1") (pinfunction "1_1") (pintype "passive"))
      (node (ref "U13") (pin "10") (pinfunction "VOUT_B_10") (pintype "bidirectional"))
    )
    (net (code "83") (name "Net-(U14-VOUT_A)") (class "Default")
      (node (ref "R48") (pin "1") (pinfunction "1_1") (pintype "passive"))
      (node (ref "U14") (pin "14") (pinfunction "VOUT_A_14") (pintype "bidirectional"))
    )
    (net (code "84") (name "Net-(U14-VOUT_B)") (class "Default")
      (node (ref "R49") (pin "1") (pinfunction "1_1") (pintype "passive"))
      (node (ref "U14") (pin "10") (pinfunction "VOUT_B_10") (pintype "bidirectional"))
    )
    (net (code "85") (name "Net-(U15A-+IN)") (class "Default")
      (node (ref "R51") (pin "2") (pinfunction "2_2") (pintype "passive"))
      (node (ref "R53") (pin "2") (pinfunction "2_2") (pintype "passive"))
      (node (ref "U15") (pin "3") (pinfunction "+IN_3") (pintype "input"))
    )
    (net (code "86") (name "Net-(U15A--IN)") (class "Default")
      (node (ref "R45") (pin "2") (pinfunction "2_2") (pintype "passive"))
      (node (ref "R57") (pin "1") (pinfunction "1_1") (pintype "passive"))
      (node (ref "U15") (pin "2") (pinfunction "-IN_2") (pintype "input"))
    )
    (net (code "87") (name "Net-(U15A-OUT)") (class "Default")
      (node (ref "R57") (pin "2") (pinfunction "2_2") (pintype "passive"))
      (node (ref "R61") (pin "1") (pinfunction "1_1") (pintype "passive"))
      (node (ref "U15") (pin "1") (pinfunction "OUT_1") (pintype "output"))
    )
    (net (code "88") (name "Net-(U15B-+IN)") (class "Default")
      (node (ref "R47") (pin "2") (pinfunction "2_2") (pintype "passive"))
      (node (ref "R54") (pin "2") (pinfunction "2_2") (pintype "passive"))
      (node (ref "U15") (pin "5") (pinfunction "+IN_5") (pintype "input"))
    )
    (net (code "89") (name "Net-(U15B--IN)") (class "Default")
      (node (ref "R46") (pin "2") (pinfunction "2_2") (pintype "passive"))
      (node (ref "R59") (pin "1") (pinfunction "1_1") (pintype "passive"))
      (node (ref "U15") (pin "6") (pinfunction "-IN_6") (pintype "input"))
    )
    (net (code "90") (name "Net-(U15B-OUT)") (class "Default")
      (node (ref "R59") (pin "2") (pinfunction "2_2") (pintype "passive"))
      (node (ref "R63") (pin "1") (pinfunction "1_1") (pintype "passive"))
      (node (ref "U15") (pin "7") (pinfunction "OUT_7") (pintype "output"))
    )
    (net (code "91") (name "Net-(U16A-+IN)") (class "Default")
      (node (ref "R52") (pin "2") (pinfunction "2_2") (pintype "passive"))
      (node (ref "R55") (pin "2") (pinfunction "2_2") (pintype "passive"))
      (node (ref "U16") (pin "3") (pinfunction "+IN_3") (pintype "input"))
    )
    (net (code "92") (name "Net-(U16A--IN)") (class "Default")
      (node (ref "R48") (pin "2") (pinfunction "2_2") (pintype "passive"))
      (node (ref "R58") (pin "1") (pinfunction "1_1") (pintype "passive"))
      (node (ref "U16") (pin "2") (pinfunction "-IN_2") (pintype "input"))
    )
    (net (code "93") (name "Net-(U16A-OUT)") (class "Default")
      (node (ref "R58") (pin "2") (pinfunction "2_2") (pintype "passive"))
      (node (ref "R62") (pin "1") (pinfunction "1_1") (pintype "passive"))
      (node (ref "U16") (pin "1") (pinfunction "OUT_1") (pintype "output"))
    )
    (net (code "94") (name "Net-(U16B-+IN)") (class "Default")
      (node (ref "R50") (pin "2") (pinfunction "2_2") (pintype "passive"))
      (node (ref "R56") (pin "2") (pinfunction "2_2") (pintype "passive"))
      (node (ref "U16") (pin "5") (pinfunction "+IN_5") (pintype "input"))
    )
    (net (code "95") (name "Net-(U16B--IN)") (class "Default")
      (node (ref "R49") (pin "2") (pinfunction "2_2") (pintype "passive"))
      (node (ref "R60") (pin "1") (pinfunction "1_1") (pintype "passive"))
      (node (ref "U16") (pin "6") (pinfunction "-IN_6") (pintype "input"))
    )
    (net (code "96") (name "Net-(U16B-OUT)") (class "Default")
      (node (ref "R60") (pin "2") (pinfunction "2_2") (pintype "passive"))
      (node (ref "R64") (pin "1") (pinfunction "1_1") (pintype "passive"))
      (node (ref "U16") (pin "7") (pinfunction "OUT_7") (pintype "output"))
    )
    (net (code "97") (name "Net-(U17A--IN)") (class "Default")
      (node (ref "C19") (pin "1") (pinfunction "1_1") (pintype "passive"))
      (node (ref "R65") (pin "2") (pinfunction "2_2") (pintype "passive"))
      (node (ref "R66") (pin "2") (pinfunction "2_2") (pintype "passive"))
      (node (ref "R73") (pin "1") (pinfunction "1_1") (pintype "passive"))
      (node (ref "U17") (pin "2") (pinfunction "-IN_2") (pintype "input"))
    )
    (net (code "98") (name "Net-(U17B-+IN)") (class "Default")
      (node (ref "R77") (pin "1") (pinfunction "1_1") (pintype "passive"))
      (node (ref "R81") (pin "2") (pinfunction "2_2") (pintype "passive"))
      (node (ref "U17") (pin "5") (pinfunction "+IN_5") (pintype "input"))
    )
    (net (code "99") (name "Net-(U18A--IN)") (class "Default")
      (node (ref "C20") (pin "1") (pinfunction "1_1") (pintype "passive"))
      (node (ref "R67") (pin "2") (pinfunction "2_2") (pintype "passive"))
      (node (ref "R68") (pin "2") (pinfunction "2_2") (pintype "passive"))
      (node (ref "R74") (pin "1") (pinfunction "1_1") (pintype "passive"))
      (node (ref "U18") (pin "2") (pinfunction "-IN_2") (pintype "input"))
    )
    (net (code "100") (name "Net-(U18B-+IN)") (class "Default")
      (node (ref "R78") (pin "1") (pinfunction "1_1") (pintype "passive"))
      (node (ref "R82") (pin "2") (pinfunction "2_2") (pintype "passive"))
      (node (ref "U18") (pin "5") (pinfunction "+IN_5") (pintype "input"))
    )
    (net (code "101") (name "Net-(U19A--IN)") (class "Default")
      (node (ref "C21") (pin "1") (pinfunction "1_1") (pintype "passive"))
      (node (ref "R69") (pin "2") (pinfunction "2_2") (pintype "passive"))
      (node (ref "R70") (pin "2") (pinfunction "2_2") (pintype "passive"))
      (node (ref "R75") (pin "1") (pinfunction "1_1") (pintype "passive"))
      (node (ref "U19") (pin "2") (pinfunction "-IN_2") (pintype "input"))
    )
    (net (code "102") (name "Net-(U19B-+IN)") (class "Default")
      (node (ref "R79") (pin "1") (pinfunction "1_1") (pintype "passive"))
      (node (ref "R83") (pin "2") (pinfunction "2_2") (pintype "passive"))
      (node (ref "U19") (pin "5") (pinfunction "+IN_5") (pintype "input"))
    )
    (net (code "103") (name "Net-(U20A--IN)") (class "Default")
      (node (ref "C22") (pin "1") (pinfunction "1_1") (pintype "passive"))
      (node (ref "R71") (pin "2") (pinfunction "2_2") (pintype "passive"))
      (node (ref "R72") (pin "2") (pinfunction "2_2") (pintype "passive"))
      (node (ref "R76") (pin "1") (pinfunction "1_1") (pintype "passive"))
      (node (ref "U20") (pin "2") (pinfunction "-IN_2") (pintype "input"))
    )
    (net (code "104") (name "Net-(U20B-+IN)") (class "Default")
      (node (ref "R80") (pin "1") (pinfunction "1_1") (pintype "passive"))
      (node (ref "R84") (pin "2") (pinfunction "2_2") (pintype "passive"))
      (node (ref "U20") (pin "5") (pinfunction "+IN_5") (pintype "input"))
    )
    (net (code "105") (name "Net-(U21-PF0{slash}OSC_IN)") (class "Default")
      (node (ref "C26") (pin "2") (pinfunction "2_2") (pintype "passive"))
      (node (ref "U21") (pin "5") (pinfunction "PF0/OSC_IN_5") (pintype "bidirectional"))
      (node (ref "X1") (pin "P$2") (pinfunction "P$2_P$2") (pintype "bidirectional"))
    )
    (net (code "106") (name "Net-(U21-PF1{slash}OSC_OUT)") (class "Default")
      (node (ref "C27") (pin "2") (pinfunction "2_2") (pintype "passive"))
      (node (ref "U21") (pin "6") (pinfunction "PF1/OSC_OUT_6") (pintype "bidirectional"))
      (node (ref "X1") (pin "P$1") (pinfunction "P$1_P$1") (pintype "bidirectional"))
    )
    (net (code "107") (name "OUT_L") (class "Default")
      (node (ref "C32") (pin "2") (pinfunction "2_2") (pintype "passive"))
      (node (ref "J19") (pin "P$1_TIP") (pinfunction "2_P$1_TIP") (pintype "passive"))
      (node (ref "JP2") (pin "1") (pinfunction "1_1") (pintype "passive"))
      (node (ref "R88") (pin "2") (pinfunction "2_2") (pintype "passive"))
      (node (ref "U22") (pin "1") (pinfunction "OUT_1") (pintype "output"))
    )
    (net (code "108") (name "OUT_R") (class "Default")
      (node (ref "C33") (pin "2") (pinfunction "2_2") (pintype "passive"))
      (node (ref "J18") (pin "P$1_TIP") (pinfunction "2_P$1_TIP") (pintype "passive"))
      (node (ref "JP2") (pin "2") (pinfunction "2_2") (pintype "passive"))
      (node (ref "R89") (pin "2") (pinfunction "2_2") (pintype "passive"))
      (node (ref "U22") (pin "7") (pinfunction "OUT_7") (pintype "output"))
    )
    (net (code "109") (name "PAN_1_POT") (class "Default")
      (node (ref "IC1") (pin "1") (pinfunction "X4_1") (pintype "bidirectional"))
      (node (ref "VR3") (pin "2") (pinfunction "S_2") (pintype "passive"))
    )
    (net (code "110") (name "PAN_2_POT") (class "Default")
      (node (ref "IC1") (pin "5") (pinfunction "X5_5") (pintype "bidirectional"))
      (node (ref "VR7") (pin "2") (pinfunction "S_2") (pintype "passive"))
    )
    (net (code "111") (name "PAN_3_POT") (class "Default")
      (node (ref "IC1") (pin "2") (pinfunction "X6_2") (pintype "bidirectional"))
      (node (ref "VR4") (pin "2") (pinfunction "S_2") (pintype "passive"))
    )
    (net (code "112") (name "PAN_4_POT") (class "Default")
      (node (ref "IC1") (pin "4") (pinfunction "X7_4") (pintype "bidirectional"))
      (node (ref "VR8") (pin "2") (pinfunction "S_2") (pintype "passive"))
    )
    (net (code "113") (name "PAN_CV_1") (class "Default")
      (node (ref "C19") (pin "2") (pinfunction "2_2") (pintype "passive"))
      (node (ref "R73") (pin "2") (pinfunction "2_2") (pintype "passive"))
      (node (ref "U17") (pin "1") (pinfunction "OUT_1") (pintype "output"))
      (node (ref "U21") (pin "14") (pinfunction "PA4/SPI1_NSS/USART2_CK/TIM14_CH1/ADC_IN4_14") (pintype "bidirectional"))
    )
    (net (code "114") (name "PAN_CV_2") (class "Default")
      (node (ref "C20") (pin "2") (pinfunction "2_2") (pintype "passive"))
      (node (ref "R74") (pin "2") (pinfunction "2_2") (pintype "passive"))
      (node (ref "U18") (pin "1") (pinfunction "OUT_1") (pintype "output"))
      (node (ref "U21") (pin "15") (pinfunction "PA5/SPI1_SCK/ADC_IN5_15") (pintype "bidirectional"))
    )
    (net (code "115") (name "PAN_CV_3") (class "Default")
      (node (ref "C21") (pin "2") (pinfunction "2_2") (pintype "passive"))
      (node (ref "R75") (pin "2") (pinfunction "2_2") (pintype "passive"))
      (node (ref "U19") (pin "1") (pinfunction "OUT_1") (pintype "output"))
      (node (ref "U21") (pin "16") (pinfunction "PA6/SPI1_MISO/TIM3_CH1/TIM1_BKIN/TIM16_CH1/EVENTOUT/ADC_IN6_16") (pintype "bidirectional"))
    )
    (net (code "116") (name "PAN_CV_4") (class "Default")
      (node (ref "C22") (pin "2") (pinfunction "2_2") (pintype "passive"))
      (node (ref "R76") (pin "2") (pinfunction "2_2") (pintype "passive"))
      (node (ref "U20") (pin "1") (pinfunction "OUT_1") (pintype "output"))
      (node (ref "U21") (pin "17") (pinfunction "PA7/SPI1_MOSI/TIM3_CH2/TIM14_CH1/TIM1_CH1N/TIM17_CH1/EVENTOUT/ADC_IN7_17") (pintype "bidirectional"))
    )
    (net (code "117") (name "POT_MUX") (class "Default")
      (node (ref "IC1") (pin "3") (pinfunction "X_3") (pintype "bidirectional"))
      (node (ref "U21") (pin "18") (pinfunction "PB0/TIM3_CH3/TIM1_CH2N/EVENTOUT/ADC_IN8_18") (pintype "bidirectional"))
    )
    (net (code "118") (name "SCK") (class "Default")
      (node (ref "U1") (pin "3") (pinfunction "SCK_3") (pintype "input"))
      (node (ref "U10") (pin "3") (pinfunction "SCK_3") (pintype "input"))
      (node (ref "U13") (pin "4") (pinfunction "SCK_4") (pintype "bidirectional"))
      (node (ref "U14") (pin "4") (pinfunction "SCK_4") (pintype "bidirectional"))
      (node (ref "U2") (pin "3") (pinfunction "SCK_3") (pintype "input"))
      (node (ref "U21") (pin "39") (pinfunction "PB3/SPI1_SCK/EVENTOUT_39") (pintype "bidirectional"))
      (node (ref "U5") (pin "4") (pinfunction "SCK_4") (pintype "bidirectional"))
      (node (ref "U6") (pin "4") (pinfunction "SCK_4") (pintype "bidirectional"))
      (node (ref "U9") (pin "3") (pinfunction "SCK_3") (pintype "input"))
    )
    (net (code "119") (name "SUM_L") (class "Default")
      (node (ref "C32") (pin "1") (pinfunction "1_1") (pintype "passive"))
      (node (ref "R29") (pin "2") (pinfunction "2_2") (pintype "passive"))
      (node (ref "R31") (pin "2") (pinfunction "2_2") (pintype "passive"))
      (node (ref "R61") (pin "2") (pinfunction "2_2") (pintype "passive"))
      (node (ref "R62") (pin "2") (pinfunction "2_2") (pintype "passive"))
      (node (ref "R86") (pin "2") (pinfunction "2_2") (pintype "passive"))
      (node (ref "R88") (pin "1") (pinfunction "1_1") (pintype "passive"))
      (node (ref "U22") (pin "2") (pinfunction "-IN_2") (pintype "input"))
    )
    (net (code "120") (name "SUM_R") (class "Default")
      (node (ref "C33") (pin "1") (pinfunction "1_1") (pintype "passive"))
      (node (ref "R30") (pin "2") (pinfunction "2_2") (pintype "passive"))
      (node (ref "R32") (pin "2") (pinfunction "2_2") (pintype "passive"))
      (node (ref "R63") (pin "2") (pinfunction "2_2") (pintype "passive"))
      (node (ref "R64") (pin "2") (pinfunction "2_2") (pintype "passive"))
      (node (ref "R87") (pin "2") (pinfunction "2_2") (pintype "passive"))
      (node (ref "R89") (pin "1") (pinfunction "1_1") (pintype "passive"))
      (node (ref "U22") (pin "6") (pinfunction "-IN_6") (pintype "input"))
    )
    (net (code "121") (name "SWDCLK") (class "Default")
      (node (ref "J17") (pin "4") (pinfunction "SWDCLK/TCK_4") (pintype "bidirectional"))
      (node (ref "U21") (pin "37") (pinfunction "PA14/USART2_TX/SWCLK_37") (pintype "bidirectional"))
    )
    (net (code "122") (name "SWDIO") (class "Default")
      (node (ref "J17") (pin "2") (pinfunction "SWDIO/TMS_2") (pintype "bidirectional"))
      (node (ref "U21") (pin "34") (pinfunction "PA13/IR_OUT/SWDIO_34") (pintype "bidirectional"))
    )
    (net (code "123") (name "VOL_1_POT") (class "Default")
      (node (ref "IC1") (pin "13") (pinfunction "X0_13") (pintype "bidirectional"))
      (node (ref "VR1") (pin "2") (pinfunction "S_2") (pintype "passive"))
    )
    (net (code "124") (name "VOL_2_POT") (class "Default")
      (node (ref "IC1") (pin "14") (pinfunction "X1_14") (pintype "bidirectional"))
      (node (ref "VR5") (pin "2") (pinfunction "S_2") (pintype "passive"))
    )
    (net (code "125") (name "VOL_3_POT") (class "Default")
      (node (ref "IC1") (pin "15") (pinfunction "X2_15") (pintype "bidirectional"))
      (node (ref "VR2") (pin "2") (pinfunction "S_2") (pintype "passive"))
    )
    (net (code "126") (name "VOL_4_POT") (class "Default")
      (node (ref "IC1") (pin "12") (pinfunction "X3_12") (pintype "bidirectional"))
      (node (ref "VR6") (pin "2") (pinfunction "S_2") (pintype "passive"))
    )
    (net (code "127") (name "VOL_CV_1") (class "Default")
      (node (ref "U17") (pin "6") (pinfunction "-IN_6") (pintype "input"))
      (node (ref "U17") (pin "7") (pinfunction "OUT_7") (pintype "output"))
      (node (ref "U21") (pin "10") (pinfunction "PA0/USART2_CTS/ADC_IN0/RTC_TAMP2/WKUP1_10") (pintype "bidirectional"))
    )
    (net (code "128") (name "VOL_CV_2") (class "Default")
      (node (ref "U18") (pin "6") (pinfunction "-IN_6") (pintype "input"))
      (node (ref "U18") (pin "7") (pinfunction "OUT_7") (pintype "output"))
      (node (ref "U21") (pin "11") (pinfunction "PA1/USART2_RTS/EVENTOUT/ADC_IN1_11") (pintype "bidirectional"))
    )
    (net (code "129") (name "VOL_CV_3") (class "Default")
      (node (ref "U19") (pin "6") (pinfunction "-IN_6") (pintype "input"))
      (node (ref "U19") (pin "7") (pinfunction "OUT_7") (pintype "output"))
      (node (ref "U21") (pin "12") (pinfunction "PA2/USART2_TX/TIM15_CH1/ADC_IN2_12") (pintype "bidirectional"))
    )
    (net (code "130") (name "VOL_CV_4") (class "Default")
      (node (ref "U20") (pin "6") (pinfunction "-IN_6") (pintype "input"))
      (node (ref "U20") (pin "7") (pinfunction "OUT_7") (pintype "output"))
      (node (ref "U21") (pin "13") (pinfunction "PA3/USART2_RX/TIM15_CH2/ADC_IN3_13") (pintype "bidirectional"))
    )
    (net (code "131") (name "unconnected-(J1-3-PadP$2_SWITCH)") (class "Default")
      (node (ref "J1") (pin "P$2_SWITCH") (pinfunction "3_P$2_SWITCH") (pintype "passive"))
    )
    (net (code "132") (name "unconnected-(J2-3-PadP$2_SWITCH)") (class "Default")
      (node (ref "J2") (pin "P$2_SWITCH") (pinfunction "3_P$2_SWITCH") (pintype "passive"))
    )
    (net (code "133") (name "unconnected-(J3-3-PadP$2_SWITCH)") (class "Default")
      (node (ref "J3") (pin "P$2_SWITCH") (pinfunction "3_P$2_SWITCH") (pintype "passive"))
    )
    (net (code "134") (name "unconnected-(J4-3-PadP$2_SWITCH)") (class "Default")
      (node (ref "J4") (pin "P$2_SWITCH") (pinfunction "3_P$2_SWITCH") (pintype "passive"))
    )
    (net (code "135") (name "unconnected-(J5-3-PadP$2_SWITCH)") (class "Default")
      (node (ref "J5") (pin "P$2_SWITCH") (pinfunction "3_P$2_SWITCH") (pintype "passive"))
    )
    (net (code "136") (name "unconnected-(J6-3-PadP$2_SWITCH)") (class "Default")
      (node (ref "J6") (pin "P$2_SWITCH") (pinfunction "3_P$2_SWITCH") (pintype "passive"))
    )
    (net (code "137") (name "unconnected-(J7-3-PadP$2_SWITCH)") (class "Default")
      (node (ref "J7") (pin "P$2_SWITCH") (pinfunction "3_P$2_SWITCH") (pintype "passive"))
    )
    (net (code "138") (name "unconnected-(J8-3-PadP$2_SWITCH)") (class "Default")
      (node (ref "J8") (pin "P$2_SWITCH") (pinfunction "3_P$2_SWITCH") (pintype "passive"))
    )
    (net (code "139") (name "unconnected-(J9-3-PadP$2_SWITCH)") (class "Default")
      (node (ref "J9") (pin "P$2_SWITCH") (pinfunction "3_P$2_SWITCH") (pintype "passive"))
    )
    (net (code "140") (name "unconnected-(J10-3-PadP$2_SWITCH)") (class "Default")
      (node (ref "J10") (pin "P$2_SWITCH") (pinfunction "3_P$2_SWITCH") (pintype "passive"))
    )
    (net (code "141") (name "unconnected-(J11-3-PadP$2_SWITCH)") (class "Default")
      (node (ref "J11") (pin "P$2_SWITCH") (pinfunction "3_P$2_SWITCH") (pintype "passive"))
    )
    (net (code "142") (name "unconnected-(J12-3-PadP$2_SWITCH)") (class "Default")
      (node (ref "J12") (pin "P$2_SWITCH") (pinfunction "3_P$2_SWITCH") (pintype "passive"))
    )
    (net (code "143") (name "unconnected-(J13-3-PadP$2_SWITCH)") (class "Default")
      (node (ref "J13") (pin "P$2_SWITCH") (pinfunction "3_P$2_SWITCH") (pintype "passive"))
    )
    (net (code "144") (name "unconnected-(J14-3-PadP$2_SWITCH)") (class "Default")
      (node (ref "J14") (pin "P$2_SWITCH") (pinfunction "3_P$2_SWITCH") (pintype "passive"))
    )
    (net (code "145") (name "unconnected-(J15-3-PadP$2_SWITCH)") (class "Default")
      (node (ref "J15") (pin "P$2_SWITCH") (pinfunction "3_P$2_SWITCH") (pintype "passive"))
    )
    (net (code "146") (name "unconnected-(J16-3-PadP$2_SWITCH)") (class "Default")
      (node (ref "J16") (pin "P$2_SWITCH") (pinfunction "3_P$2_SWITCH") (pintype "passive"))
    )
    (net (code "147") (name "unconnected-(J17-KEY-Pad7)") (class "Default")
      (node (ref "J17") (pin "7") (pinfunction "KEY_7") (pintype "bidirectional"))
    )
    (net (code "148") (name "unconnected-(J17-NC{slash}TDI-Pad8)") (class "Default")
      (node (ref "J17") (pin "8") (pinfunction "NC/TDI_8") (pintype "bidirectional"))
    )
    (net (code "149") (name "unconnected-(J17-SWO{slash}TDO-Pad6)") (class "Default")
      (node (ref "J17") (pin "6") (pinfunction "SWO/TDO_6") (pintype "bidirectional"))
    )
    (net (code "150") (name "unconnected-(J18-3-PadP$2_SWITCH)") (class "Default")
      (node (ref "J18") (pin "P$2_SWITCH") (pinfunction "3_P$2_SWITCH") (pintype "passive"))
    )
    (net (code "151") (name "unconnected-(J19-3-PadP$2_SWITCH)") (class "Default")
      (node (ref "J19") (pin "P$2_SWITCH") (pinfunction "3_P$2_SWITCH") (pintype "passive"))
    )
    (net (code "152") (name "unconnected-(U21-PA12{slash}USART1_RTS{slash}TIM1_ETR{slash}EVENTOUT-Pad33)") (class "Default")
      (node (ref "U21") (pin "33") (pinfunction "PA12/USART1_RTS/TIM1_ETR/EVENTOUT_33") (pintype "bidirectional"))
    )
    (net (code "153") (name "unconnected-(U21-PA15{slash}SPI1_NSS{slash}USART2_RX{slash}EVENTOUT-Pad38)") (class "Default")
      (node (ref "U21") (pin "38") (pinfunction "PA15/SPI1_NSS/USART2_RX/EVENTOUT_38") (pintype "bidirectional"))
    )
    (net (code "154") (name "unconnected-(U21-PB1{slash}TIM3_CH4{slash}TIM14_CH1{slash}TIM1_CH3N{slash}ADC_IN9-Pad19)") (class "Default")
      (node (ref "U21") (pin "19") (pinfunction "PB1/TIM3_CH4/TIM14_CH1/TIM1_CH3N/ADC_IN9_19") (pintype "bidirectional"))
    )
    (net (code "155") (name "unconnected-(U21-PB2-Pad20)") (class "Default")
      (node (ref "U21") (pin "20") (pinfunction "PB2_20") (pintype "bidirectional"))
    )
    (net (code "156") (name "unconnected-(U21-PB6{slash}I2C1_SCL{slash}USART1_TX{slash}TIM16_CH1N-Pad42)") (class "Default")
      (node (ref "U21") (pin "42") (pinfunction "PB6/I2C1_SCL/USART1_TX/TIM16_CH1N_42") (pintype "bidirectional"))
    )
    (net (code "157") (name "unconnected-(U21-PB7{slash}I2C1_SDA{slash}USART1_RX{slash}TIM17_CH1N-Pad43)") (class "Default")
      (node (ref "U21") (pin "43") (pinfunction "PB7/I2C1_SDA/USART1_RX/TIM17_CH1N_43") (pintype "bidirectional"))
    )
    (net (code "158") (name "unconnected-(U21-PB15{slash}SPI2_MOSI{slash}TIM1_CH3N{slash}TIM15_CH1N{slash}TIM15_CH2{slash}RTC_REFIN-Pad28)") (class "Default")
      (node (ref "U21") (pin "28") (pinfunction "PB15/SPI2_MOSI/TIM1_CH3N/TIM15_CH1N/TIM15_CH2/RTC_REFIN_28") (pintype "bidirectional"))
    )
    (net (code "159") (name "unconnected-(U21-PC13{slash}RTC_TAMP1{slash}RTC_TS{slash}RTC_OUT{slash}WKUP2-Pad2)") (class "Default")
      (node (ref "U21") (pin "2") (pinfunction "PC13/RTC_TAMP1/RTC_TS/RTC_OUT/WKUP2_2") (pintype "bidirectional"))
    )
    (net (code "160") (name "unconnected-(U21-PC14{slash}OSC32_IN-Pad3)") (class "Default")
      (node (ref "U21") (pin "3") (pinfunction "PC14/OSC32_IN_3") (pintype "bidirectional"))
    )
    (net (code "161") (name "unconnected-(U21-PC15{slash}OSC32_OUT-Pad4)") (class "Default")
      (node (ref "U21") (pin "4") (pinfunction "PC15/OSC32_OUT_4") (pintype "bidirectional"))
    )
    (net (code "162") (name "unconnected-(U21-PF6{slash}I2C2_SCL-Pad35)") (class "Default")
      (node (ref "U21") (pin "35") (pinfunction "PF6/I2C2_SCL_35") (pintype "bidirectional"))
    )
    (net (code "163") (name "unconnected-(U21-PF7{slash}I2C2_SDA-Pad36)") (class "Default")
      (node (ref "U21") (pin "36") (pinfunction "PF7/I2C2_SDA_36") (pintype "bidirectional"))
    )
  )
)
